# HashUnit3.net
KiCad netlist of a schematic drawn in Altium Designer
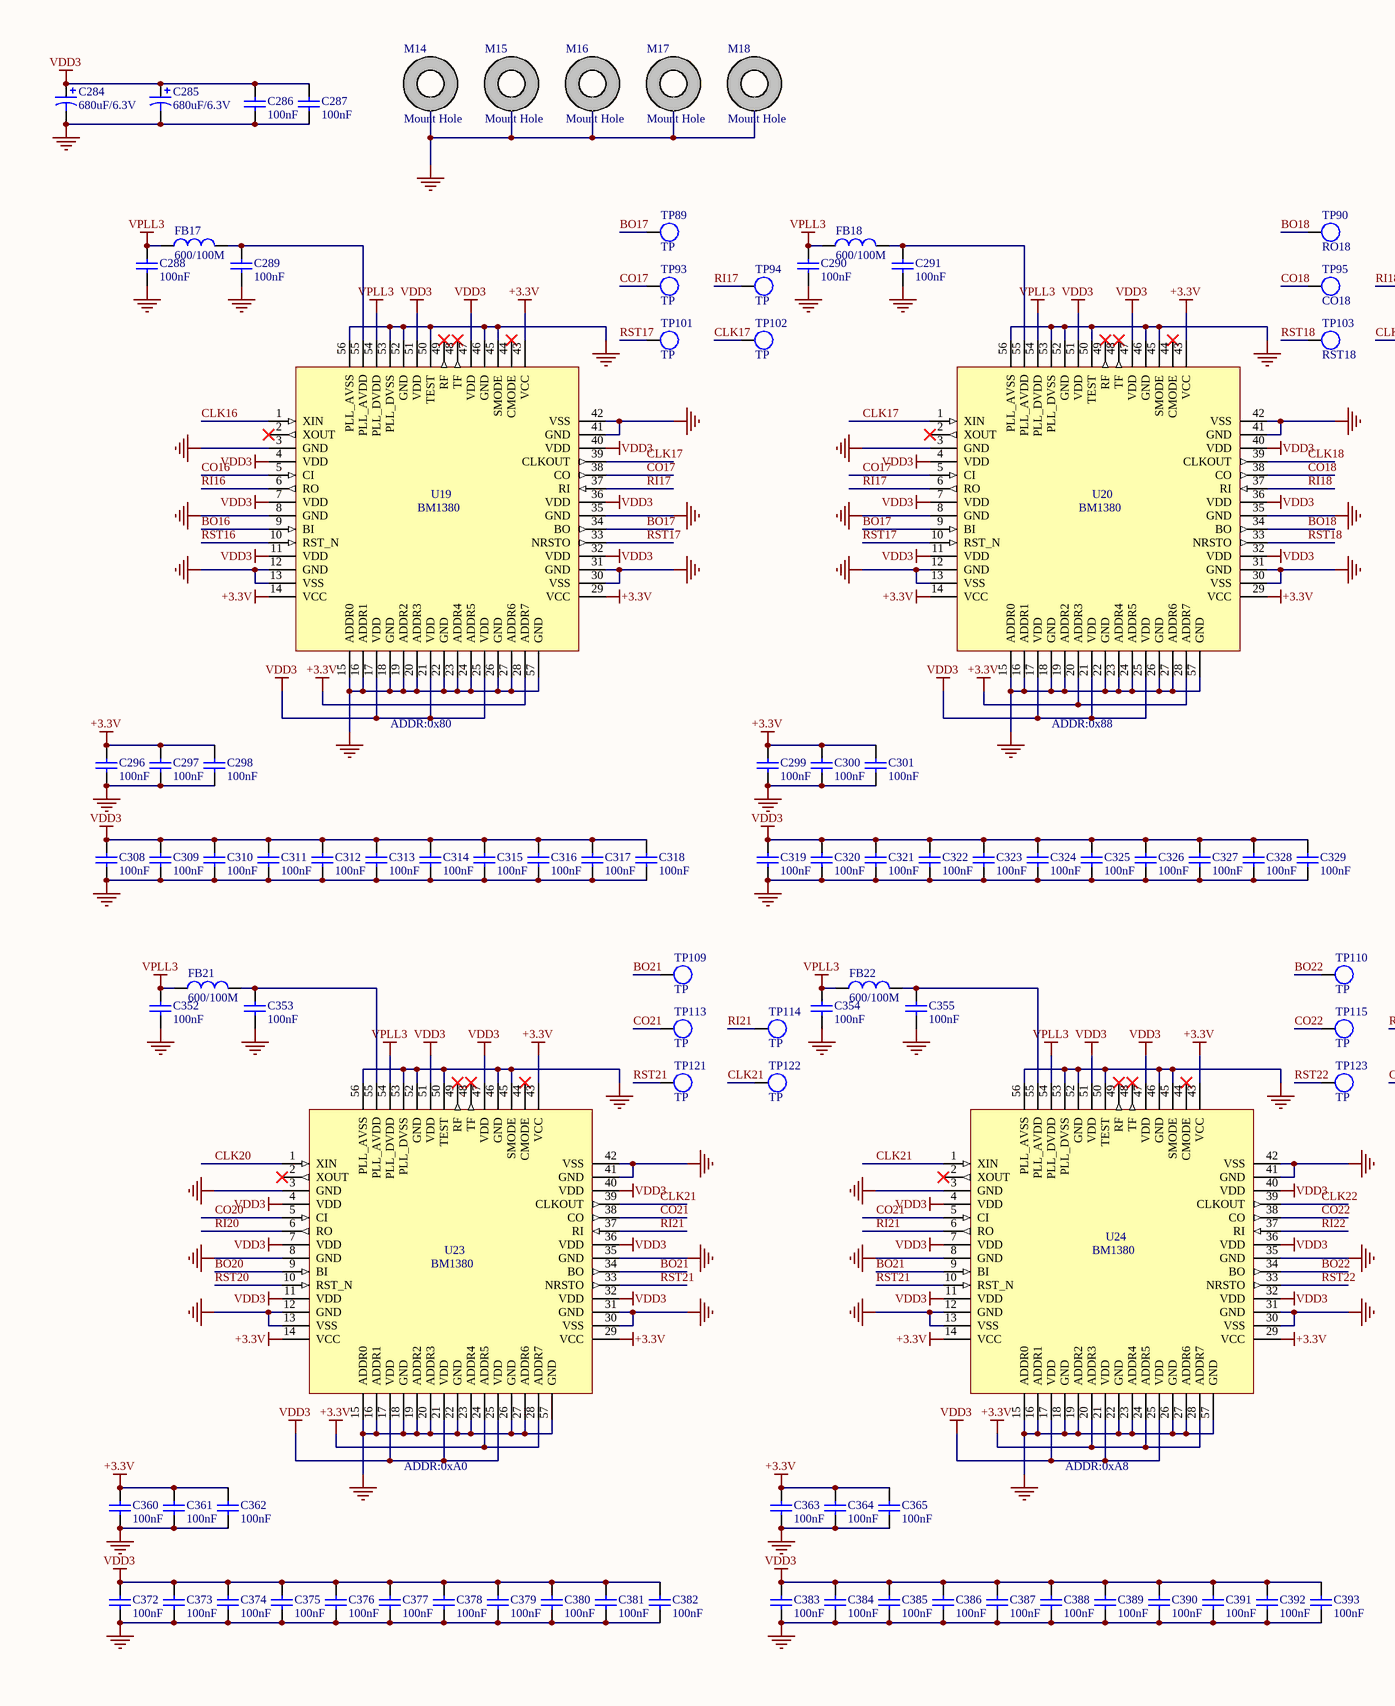
[diagram p0: HashUnit3.SchDoc, left]
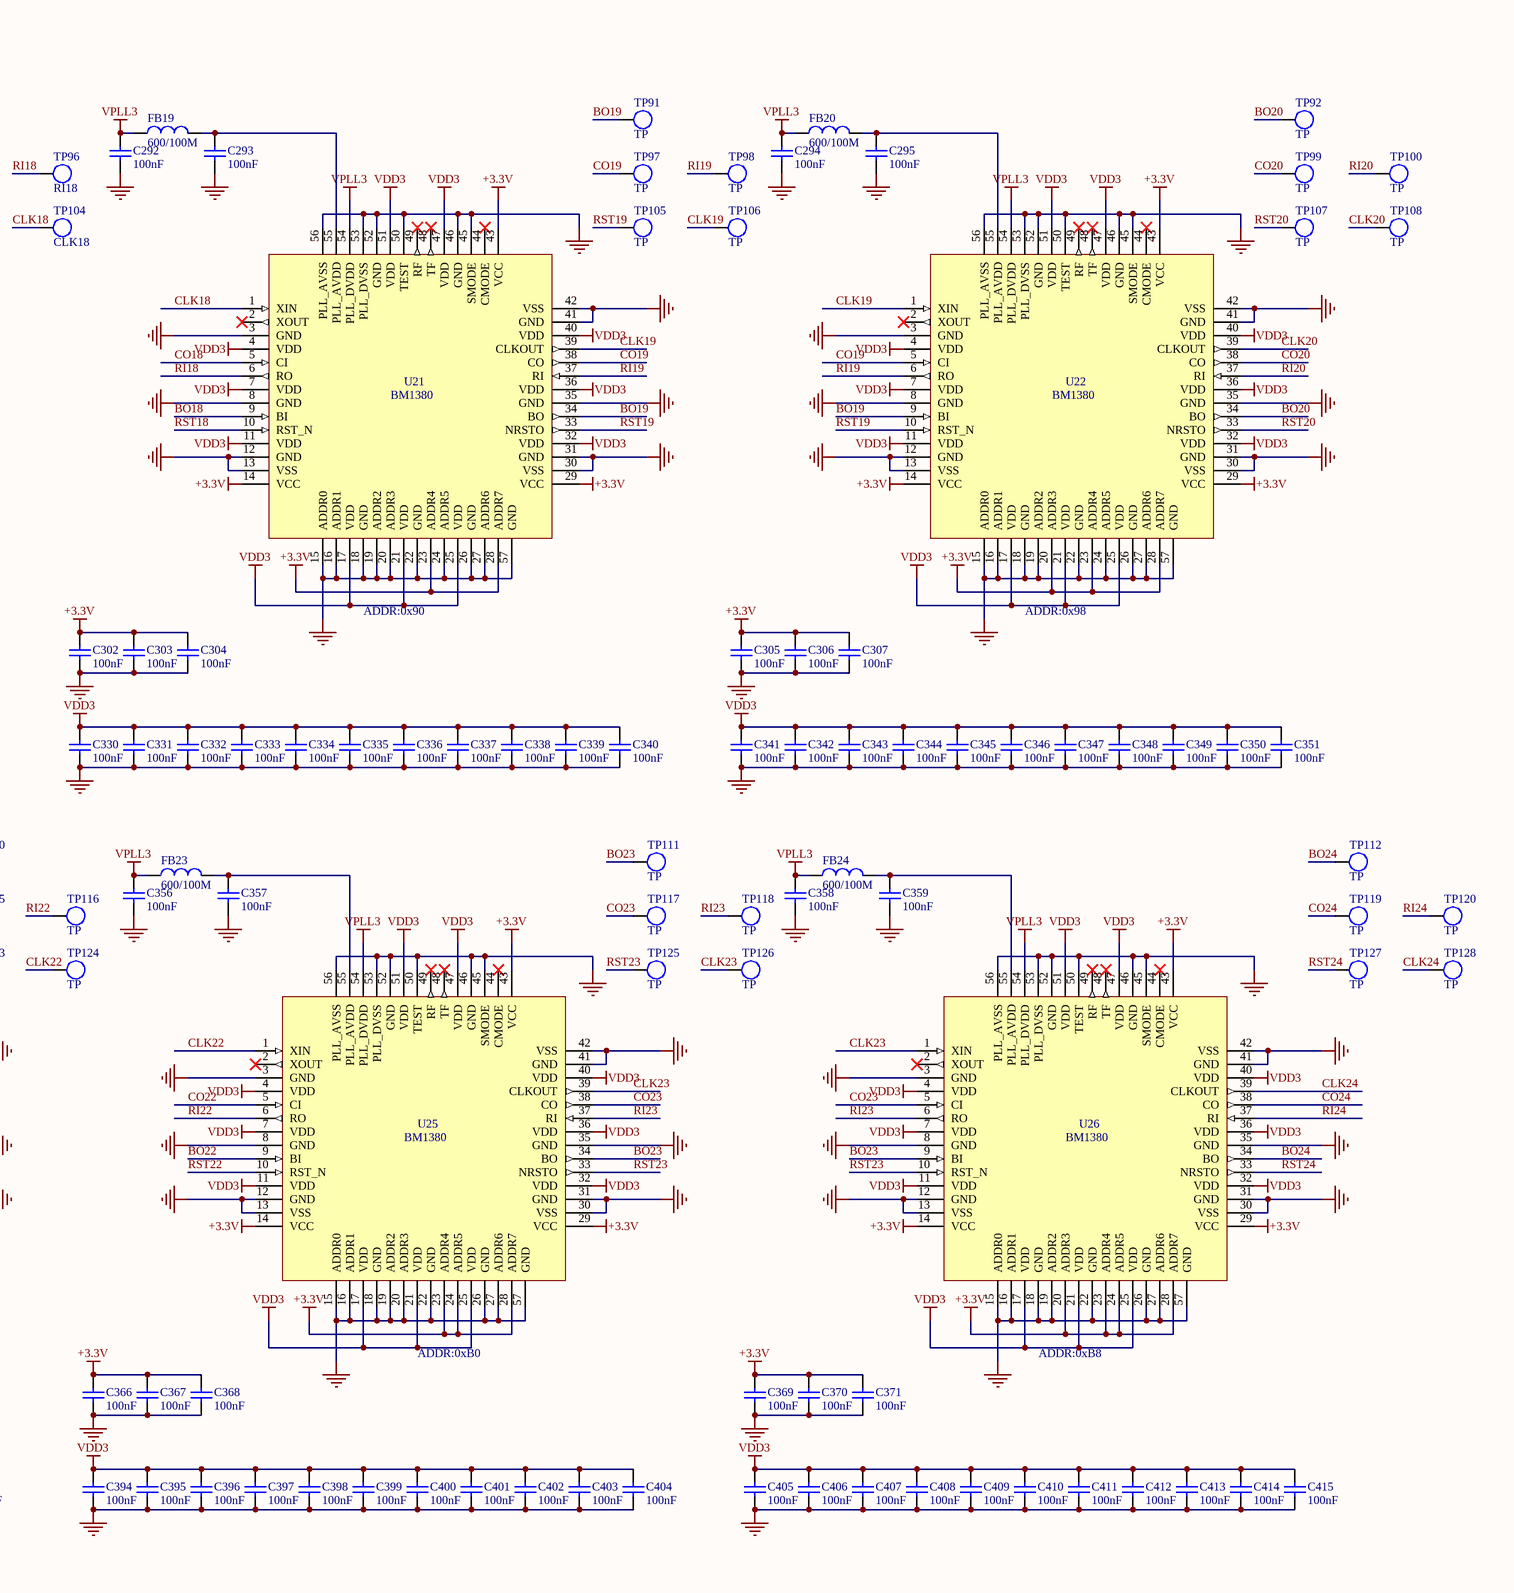
[diagram p1: HashUnit3.SchDoc, right]

(export (version "E")
  (design (tool "Eeschema 10.0.6"))
  (components
    (comp (ref "C284")
      (value "680uF/6.3V")
      (footprint "D")
      (description "Solid Tantalum Chip Capacitor, T492 Series - CWR11 Style Per Mil-PRF-55365/8")
      (fields (field (name "PUBLISHER") "Altium Limited"))
      (libsource (lib "KEMET Chip Capacitor") (part "T492C"))
    )
    (comp (ref "C285")
      (value "680uF/6.3V")
      (footprint "D")
      (description "Solid Tantalum Chip Capacitor, T492 Series - CWR11 Style Per Mil-PRF-55365/8")
      (fields (field (name "PUBLISHER") "Altium Limited"))
      (libsource (lib "KEMET Chip Capacitor") (part "T492C"))
    )
    (comp (ref "C286")
      (value "100nF")
      (footprint "CC0603(1608)")
      (description "Capacitor (Semiconductor SIM Model)")
      (fields (field (name "PUBLISHER") "Altium Limited"))
      (libsource (lib "Miscellaneous Devices") (part "Cap Semi"))
    )
    (comp (ref "C287")
      (value "100nF")
      (footprint "CC0603(1608)")
      (description "Capacitor (Semiconductor SIM Model)")
      (fields (field (name "PUBLISHER") "Altium Limited"))
      (libsource (lib "Miscellaneous Devices") (part "Cap Semi"))
    )
    (comp (ref "C288")
      (value "100nF")
      (footprint "CC0603(1608)")
      (description "Capacitor")
      (fields (field (name "PUBLISHER") "Altium Limited"))
      (libsource (lib "BitMain_Miner_1") (part "Cap"))
    )
    (comp (ref "C289")
      (value "100nF")
      (footprint "CC0603(1608)")
      (description "Capacitor")
      (fields (field (name "PUBLISHER") "Altium Limited"))
      (libsource (lib "BitMain_Miner_1") (part "Cap"))
    )
    (comp (ref "C290")
      (value "100nF")
      (footprint "CC0603(1608)")
      (description "Capacitor")
      (fields (field (name "PUBLISHER") "Altium Limited"))
      (libsource (lib "BitMain_Miner_1") (part "Cap"))
    )
    (comp (ref "C291")
      (value "100nF")
      (footprint "CC0603(1608)")
      (description "Capacitor")
      (fields (field (name "PUBLISHER") "Altium Limited"))
      (libsource (lib "BitMain_Miner_1") (part "Cap"))
    )
    (comp (ref "C292")
      (value "100nF")
      (footprint "CC0603(1608)")
      (description "Capacitor")
      (fields (field (name "PUBLISHER") "Altium Limited"))
      (libsource (lib "BitMain_Miner_1") (part "Cap"))
    )
    (comp (ref "C293")
      (value "100nF")
      (footprint "CC0603(1608)")
      (description "Capacitor")
      (fields (field (name "PUBLISHER") "Altium Limited"))
      (libsource (lib "BitMain_Miner_1") (part "Cap"))
    )
    (comp (ref "C294")
      (value "100nF")
      (footprint "CC0603(1608)")
      (description "Capacitor")
      (fields (field (name "PUBLISHER") "Altium Limited"))
      (libsource (lib "BitMain_Miner_1") (part "Cap"))
    )
    (comp (ref "C295")
      (value "100nF")
      (footprint "CC0603(1608)")
      (description "Capacitor")
      (fields (field (name "PUBLISHER") "Altium Limited"))
      (libsource (lib "BitMain_Miner_1") (part "Cap"))
    )
    (comp (ref "C296")
      (value "100nF")
      (footprint "CC0603(1608)")
      (description "Capacitor")
      (fields (field (name "PUBLISHER") "Altium Limited"))
      (libsource (lib "BitMain_Miner_1") (part "Cap"))
    )
    (comp (ref "C297")
      (value "100nF")
      (footprint "CC0603(1608)")
      (description "Capacitor")
      (fields (field (name "PUBLISHER") "Altium Limited"))
      (libsource (lib "BitMain_Miner_1") (part "Cap"))
    )
    (comp (ref "C298")
      (value "100nF")
      (footprint "CC0603(1608)")
      (description "Capacitor")
      (fields (field (name "PUBLISHER") "Altium Limited"))
      (libsource (lib "BitMain_Miner_1") (part "Cap"))
    )
    (comp (ref "C299")
      (value "100nF")
      (footprint "CC0603(1608)")
      (description "Capacitor")
      (fields (field (name "PUBLISHER") "Altium Limited"))
      (libsource (lib "BitMain_Miner_1") (part "Cap"))
    )
    (comp (ref "C300")
      (value "100nF")
      (footprint "CC0603(1608)")
      (description "Capacitor")
      (fields (field (name "PUBLISHER") "Altium Limited"))
      (libsource (lib "BitMain_Miner_1") (part "Cap"))
    )
    (comp (ref "C301")
      (value "100nF")
      (footprint "CC0603(1608)")
      (description "Capacitor")
      (fields (field (name "PUBLISHER") "Altium Limited"))
      (libsource (lib "BitMain_Miner_1") (part "Cap"))
    )
    (comp (ref "C302")
      (value "100nF")
      (footprint "CC0603(1608)")
      (description "Capacitor")
      (fields (field (name "PUBLISHER") "Altium Limited"))
      (libsource (lib "BitMain_Miner_1") (part "Cap"))
    )
    (comp (ref "C303")
      (value "100nF")
      (footprint "CC0603(1608)")
      (description "Capacitor")
      (fields (field (name "PUBLISHER") "Altium Limited"))
      (libsource (lib "BitMain_Miner_1") (part "Cap"))
    )
    (comp (ref "C304")
      (value "100nF")
      (footprint "CC0603(1608)")
      (description "Capacitor")
      (fields (field (name "PUBLISHER") "Altium Limited"))
      (libsource (lib "BitMain_Miner_1") (part "Cap"))
    )
    (comp (ref "C305")
      (value "100nF")
      (footprint "CC0603(1608)")
      (description "Capacitor")
      (fields (field (name "PUBLISHER") "Altium Limited"))
      (libsource (lib "BitMain_Miner_1") (part "Cap"))
    )
    (comp (ref "C306")
      (value "100nF")
      (footprint "CC0603(1608)")
      (description "Capacitor")
      (fields (field (name "PUBLISHER") "Altium Limited"))
      (libsource (lib "BitMain_Miner_1") (part "Cap"))
    )
    (comp (ref "C307")
      (value "100nF")
      (footprint "CC0603(1608)")
      (description "Capacitor")
      (fields (field (name "PUBLISHER") "Altium Limited"))
      (libsource (lib "BitMain_Miner_1") (part "Cap"))
    )
    (comp (ref "C308")
      (value "100nF")
      (footprint "CC0603(1608)")
      (description "Capacitor")
      (fields (field (name "PUBLISHER") "Altium Limited"))
      (libsource (lib "BitMain_Miner_1") (part "Cap"))
    )
    (comp (ref "C309")
      (value "100nF")
      (footprint "CC0603(1608)")
      (description "Capacitor")
      (fields (field (name "PUBLISHER") "Altium Limited"))
      (libsource (lib "BitMain_Miner_1") (part "Cap"))
    )
    (comp (ref "C310")
      (value "100nF")
      (footprint "CC0603(1608)")
      (description "Capacitor")
      (fields (field (name "PUBLISHER") "Altium Limited"))
      (libsource (lib "BitMain_Miner_1") (part "Cap"))
    )
    (comp (ref "C311")
      (value "100nF")
      (footprint "CC0603(1608)")
      (description "Capacitor")
      (fields (field (name "PUBLISHER") "Altium Limited"))
      (libsource (lib "BitMain_Miner_1") (part "Cap"))
    )
    (comp (ref "C312")
      (value "100nF")
      (footprint "CC0603(1608)")
      (description "Capacitor")
      (fields (field (name "PUBLISHER") "Altium Limited"))
      (libsource (lib "BitMain_Miner_1") (part "Cap"))
    )
    (comp (ref "C313")
      (value "100nF")
      (footprint "CC0603(1608)")
      (description "Capacitor")
      (fields (field (name "PUBLISHER") "Altium Limited"))
      (libsource (lib "BitMain_Miner_1") (part "Cap"))
    )
    (comp (ref "C314")
      (value "100nF")
      (footprint "CC0603(1608)")
      (description "Capacitor")
      (fields (field (name "PUBLISHER") "Altium Limited"))
      (libsource (lib "BitMain_Miner_1") (part "Cap"))
    )
    (comp (ref "C315")
      (value "100nF")
      (footprint "CC0603(1608)")
      (description "Capacitor")
      (fields (field (name "PUBLISHER") "Altium Limited"))
      (libsource (lib "BitMain_Miner_1") (part "Cap"))
    )
    (comp (ref "C316")
      (value "100nF")
      (footprint "CC0603(1608)")
      (description "Capacitor")
      (fields (field (name "PUBLISHER") "Altium Limited"))
      (libsource (lib "BitMain_Miner_1") (part "Cap"))
    )
    (comp (ref "C317")
      (value "100nF")
      (footprint "CC0603(1608)")
      (description "Capacitor")
      (fields (field (name "PUBLISHER") "Altium Limited"))
      (libsource (lib "BitMain_Miner_1") (part "Cap"))
    )
    (comp (ref "C318")
      (value "100nF")
      (footprint "CC0603(1608)")
      (description "Capacitor")
      (fields (field (name "PUBLISHER") "Altium Limited"))
      (libsource (lib "BitMain_Miner_1") (part "Cap"))
    )
    (comp (ref "C319")
      (value "100nF")
      (footprint "CC0603(1608)")
      (description "Capacitor")
      (fields (field (name "PUBLISHER") "Altium Limited"))
      (libsource (lib "BitMain_Miner_1") (part "Cap"))
    )
    (comp (ref "C320")
      (value "100nF")
      (footprint "CC0603(1608)")
      (description "Capacitor")
      (fields (field (name "PUBLISHER") "Altium Limited"))
      (libsource (lib "BitMain_Miner_1") (part "Cap"))
    )
    (comp (ref "C321")
      (value "100nF")
      (footprint "CC0603(1608)")
      (description "Capacitor")
      (fields (field (name "PUBLISHER") "Altium Limited"))
      (libsource (lib "BitMain_Miner_1") (part "Cap"))
    )
    (comp (ref "C322")
      (value "100nF")
      (footprint "CC0603(1608)")
      (description "Capacitor")
      (fields (field (name "PUBLISHER") "Altium Limited"))
      (libsource (lib "BitMain_Miner_1") (part "Cap"))
    )
    (comp (ref "C323")
      (value "100nF")
      (footprint "CC0603(1608)")
      (description "Capacitor")
      (fields (field (name "PUBLISHER") "Altium Limited"))
      (libsource (lib "BitMain_Miner_1") (part "Cap"))
    )
    (comp (ref "C324")
      (value "100nF")
      (footprint "CC0603(1608)")
      (description "Capacitor")
      (fields (field (name "PUBLISHER") "Altium Limited"))
      (libsource (lib "BitMain_Miner_1") (part "Cap"))
    )
    (comp (ref "C325")
      (value "100nF")
      (footprint "CC0603(1608)")
      (description "Capacitor")
      (fields (field (name "PUBLISHER") "Altium Limited"))
      (libsource (lib "BitMain_Miner_1") (part "Cap"))
    )
    (comp (ref "C326")
      (value "100nF")
      (footprint "CC0603(1608)")
      (description "Capacitor")
      (fields (field (name "PUBLISHER") "Altium Limited"))
      (libsource (lib "BitMain_Miner_1") (part "Cap"))
    )
    (comp (ref "C327")
      (value "100nF")
      (footprint "CC0603(1608)")
      (description "Capacitor")
      (fields (field (name "PUBLISHER") "Altium Limited"))
      (libsource (lib "BitMain_Miner_1") (part "Cap"))
    )
    (comp (ref "C328")
      (value "100nF")
      (footprint "CC0603(1608)")
      (description "Capacitor")
      (fields (field (name "PUBLISHER") "Altium Limited"))
      (libsource (lib "BitMain_Miner_1") (part "Cap"))
    )
    (comp (ref "C329")
      (value "100nF")
      (footprint "CC0603(1608)")
      (description "Capacitor")
      (fields (field (name "PUBLISHER") "Altium Limited"))
      (libsource (lib "BitMain_Miner_1") (part "Cap"))
    )
    (comp (ref "C330")
      (value "100nF")
      (footprint "CC0603(1608)")
      (description "Capacitor")
      (fields (field (name "PUBLISHER") "Altium Limited"))
      (libsource (lib "BitMain_Miner_1") (part "Cap"))
    )
    (comp (ref "C331")
      (value "100nF")
      (footprint "CC0603(1608)")
      (description "Capacitor")
      (fields (field (name "PUBLISHER") "Altium Limited"))
      (libsource (lib "BitMain_Miner_1") (part "Cap"))
    )
    (comp (ref "C332")
      (value "100nF")
      (footprint "CC0603(1608)")
      (description "Capacitor")
      (fields (field (name "PUBLISHER") "Altium Limited"))
      (libsource (lib "BitMain_Miner_1") (part "Cap"))
    )
    (comp (ref "C333")
      (value "100nF")
      (footprint "CC0603(1608)")
      (description "Capacitor")
      (fields (field (name "PUBLISHER") "Altium Limited"))
      (libsource (lib "BitMain_Miner_1") (part "Cap"))
    )
    (comp (ref "C334")
      (value "100nF")
      (footprint "CC0603(1608)")
      (description "Capacitor")
      (fields (field (name "PUBLISHER") "Altium Limited"))
      (libsource (lib "BitMain_Miner_1") (part "Cap"))
    )
    (comp (ref "C335")
      (value "100nF")
      (footprint "CC0603(1608)")
      (description "Capacitor")
      (fields (field (name "PUBLISHER") "Altium Limited"))
      (libsource (lib "BitMain_Miner_1") (part "Cap"))
    )
    (comp (ref "C336")
      (value "100nF")
      (footprint "CC0603(1608)")
      (description "Capacitor")
      (fields (field (name "PUBLISHER") "Altium Limited"))
      (libsource (lib "BitMain_Miner_1") (part "Cap"))
    )
    (comp (ref "C337")
      (value "100nF")
      (footprint "CC0603(1608)")
      (description "Capacitor")
      (fields (field (name "PUBLISHER") "Altium Limited"))
      (libsource (lib "BitMain_Miner_1") (part "Cap"))
    )
    (comp (ref "C338")
      (value "100nF")
      (footprint "CC0603(1608)")
      (description "Capacitor")
      (fields (field (name "PUBLISHER") "Altium Limited"))
      (libsource (lib "BitMain_Miner_1") (part "Cap"))
    )
    (comp (ref "C339")
      (value "100nF")
      (footprint "CC0603(1608)")
      (description "Capacitor")
      (fields (field (name "PUBLISHER") "Altium Limited"))
      (libsource (lib "BitMain_Miner_1") (part "Cap"))
    )
    (comp (ref "C340")
      (value "100nF")
      (footprint "CC0603(1608)")
      (description "Capacitor")
      (fields (field (name "PUBLISHER") "Altium Limited"))
      (libsource (lib "BitMain_Miner_1") (part "Cap"))
    )
    (comp (ref "C341")
      (value "100nF")
      (footprint "CC0603(1608)")
      (description "Capacitor")
      (fields (field (name "PUBLISHER") "Altium Limited"))
      (libsource (lib "BitMain_Miner_1") (part "Cap"))
    )
    (comp (ref "C342")
      (value "100nF")
      (footprint "CC0603(1608)")
      (description "Capacitor")
      (fields (field (name "PUBLISHER") "Altium Limited"))
      (libsource (lib "BitMain_Miner_1") (part "Cap"))
    )
    (comp (ref "C343")
      (value "100nF")
      (footprint "CC0603(1608)")
      (description "Capacitor")
      (fields (field (name "PUBLISHER") "Altium Limited"))
      (libsource (lib "BitMain_Miner_1") (part "Cap"))
    )
    (comp (ref "C344")
      (value "100nF")
      (footprint "CC0603(1608)")
      (description "Capacitor")
      (fields (field (name "PUBLISHER") "Altium Limited"))
      (libsource (lib "BitMain_Miner_1") (part "Cap"))
    )
    (comp (ref "C345")
      (value "100nF")
      (footprint "CC0603(1608)")
      (description "Capacitor")
      (fields (field (name "PUBLISHER") "Altium Limited"))
      (libsource (lib "BitMain_Miner_1") (part "Cap"))
    )
    (comp (ref "C346")
      (value "100nF")
      (footprint "CC0603(1608)")
      (description "Capacitor")
      (fields (field (name "PUBLISHER") "Altium Limited"))
      (libsource (lib "BitMain_Miner_1") (part "Cap"))
    )
    (comp (ref "C347")
      (value "100nF")
      (footprint "CC0603(1608)")
      (description "Capacitor")
      (fields (field (name "PUBLISHER") "Altium Limited"))
      (libsource (lib "BitMain_Miner_1") (part "Cap"))
    )
    (comp (ref "C348")
      (value "100nF")
      (footprint "CC0603(1608)")
      (description "Capacitor")
      (fields (field (name "PUBLISHER") "Altium Limited"))
      (libsource (lib "BitMain_Miner_1") (part "Cap"))
    )
    (comp (ref "C349")
      (value "100nF")
      (footprint "CC0603(1608)")
      (description "Capacitor")
      (fields (field (name "PUBLISHER") "Altium Limited"))
      (libsource (lib "BitMain_Miner_1") (part "Cap"))
    )
    (comp (ref "C350")
      (value "100nF")
      (footprint "CC0603(1608)")
      (description "Capacitor")
      (fields (field (name "PUBLISHER") "Altium Limited"))
      (libsource (lib "BitMain_Miner_1") (part "Cap"))
    )
    (comp (ref "C351")
      (value "100nF")
      (footprint "CC0603(1608)")
      (description "Capacitor")
      (fields (field (name "PUBLISHER") "Altium Limited"))
      (libsource (lib "BitMain_Miner_1") (part "Cap"))
    )
    (comp (ref "C352")
      (value "100nF")
      (footprint "CC0603(1608)")
      (description "Capacitor")
      (fields (field (name "PUBLISHER") "Altium Limited"))
      (libsource (lib "BitMain_Miner_1") (part "Cap"))
    )
    (comp (ref "C353")
      (value "100nF")
      (footprint "CC0603(1608)")
      (description "Capacitor")
      (fields (field (name "PUBLISHER") "Altium Limited"))
      (libsource (lib "BitMain_Miner_1") (part "Cap"))
    )
    (comp (ref "C354")
      (value "100nF")
      (footprint "CC0603(1608)")
      (description "Capacitor")
      (fields (field (name "PUBLISHER") "Altium Limited"))
      (libsource (lib "BitMain_Miner_1") (part "Cap"))
    )
    (comp (ref "C355")
      (value "100nF")
      (footprint "CC0603(1608)")
      (description "Capacitor")
      (fields (field (name "PUBLISHER") "Altium Limited"))
      (libsource (lib "BitMain_Miner_1") (part "Cap"))
    )
    (comp (ref "C356")
      (value "100nF")
      (footprint "CC0603(1608)")
      (description "Capacitor")
      (fields (field (name "PUBLISHER") "Altium Limited"))
      (libsource (lib "BitMain_Miner_1") (part "Cap"))
    )
    (comp (ref "C357")
      (value "100nF")
      (footprint "CC0603(1608)")
      (description "Capacitor")
      (fields (field (name "PUBLISHER") "Altium Limited"))
      (libsource (lib "BitMain_Miner_1") (part "Cap"))
    )
    (comp (ref "C358")
      (value "100nF")
      (footprint "CC0603(1608)")
      (description "Capacitor")
      (fields (field (name "PUBLISHER") "Altium Limited"))
      (libsource (lib "BitMain_Miner_1") (part "Cap"))
    )
    (comp (ref "C359")
      (value "100nF")
      (footprint "CC0603(1608)")
      (description "Capacitor")
      (fields (field (name "PUBLISHER") "Altium Limited"))
      (libsource (lib "BitMain_Miner_1") (part "Cap"))
    )
    (comp (ref "C360")
      (value "100nF")
      (footprint "CC0603(1608)")
      (description "Capacitor")
      (fields (field (name "PUBLISHER") "Altium Limited"))
      (libsource (lib "BitMain_Miner_1") (part "Cap"))
    )
    (comp (ref "C361")
      (value "100nF")
      (footprint "CC0603(1608)")
      (description "Capacitor")
      (fields (field (name "PUBLISHER") "Altium Limited"))
      (libsource (lib "BitMain_Miner_1") (part "Cap"))
    )
    (comp (ref "C362")
      (value "100nF")
      (footprint "CC0603(1608)")
      (description "Capacitor")
      (fields (field (name "PUBLISHER") "Altium Limited"))
      (libsource (lib "BitMain_Miner_1") (part "Cap"))
    )
    (comp (ref "C363")
      (value "100nF")
      (footprint "CC0603(1608)")
      (description "Capacitor")
      (fields (field (name "PUBLISHER") "Altium Limited"))
      (libsource (lib "BitMain_Miner_1") (part "Cap"))
    )
    (comp (ref "C364")
      (value "100nF")
      (footprint "CC0603(1608)")
      (description "Capacitor")
      (fields (field (name "PUBLISHER") "Altium Limited"))
      (libsource (lib "BitMain_Miner_1") (part "Cap"))
    )
    (comp (ref "C365")
      (value "100nF")
      (footprint "CC0603(1608)")
      (description "Capacitor")
      (fields (field (name "PUBLISHER") "Altium Limited"))
      (libsource (lib "BitMain_Miner_1") (part "Cap"))
    )
    (comp (ref "C366")
      (value "100nF")
      (footprint "CC0603(1608)")
      (description "Capacitor")
      (fields (field (name "PUBLISHER") "Altium Limited"))
      (libsource (lib "BitMain_Miner_1") (part "Cap"))
    )
    (comp (ref "C367")
      (value "100nF")
      (footprint "CC0603(1608)")
      (description "Capacitor")
      (fields (field (name "PUBLISHER") "Altium Limited"))
      (libsource (lib "BitMain_Miner_1") (part "Cap"))
    )
    (comp (ref "C368")
      (value "100nF")
      (footprint "CC0603(1608)")
      (description "Capacitor")
      (fields (field (name "PUBLISHER") "Altium Limited"))
      (libsource (lib "BitMain_Miner_1") (part "Cap"))
    )
    (comp (ref "C369")
      (value "100nF")
      (footprint "CC0603(1608)")
      (description "Capacitor")
      (fields (field (name "PUBLISHER") "Altium Limited"))
      (libsource (lib "BitMain_Miner_1") (part "Cap"))
    )
    (comp (ref "C370")
      (value "100nF")
      (footprint "CC0603(1608)")
      (description "Capacitor")
      (fields (field (name "PUBLISHER") "Altium Limited"))
      (libsource (lib "BitMain_Miner_1") (part "Cap"))
    )
    (comp (ref "C371")
      (value "100nF")
      (footprint "CC0603(1608)")
      (description "Capacitor")
      (fields (field (name "PUBLISHER") "Altium Limited"))
      (libsource (lib "BitMain_Miner_1") (part "Cap"))
    )
    (comp (ref "C372")
      (value "100nF")
      (footprint "CC0603(1608)")
      (description "Capacitor")
      (fields (field (name "PUBLISHER") "Altium Limited"))
      (libsource (lib "BitMain_Miner_1") (part "Cap"))
    )
    (comp (ref "C373")
      (value "100nF")
      (footprint "CC0603(1608)")
      (description "Capacitor")
      (fields (field (name "PUBLISHER") "Altium Limited"))
      (libsource (lib "BitMain_Miner_1") (part "Cap"))
    )
    (comp (ref "C374")
      (value "100nF")
      (footprint "CC0603(1608)")
      (description "Capacitor")
      (fields (field (name "PUBLISHER") "Altium Limited"))
      (libsource (lib "BitMain_Miner_1") (part "Cap"))
    )
    (comp (ref "C375")
      (value "100nF")
      (footprint "CC0603(1608)")
      (description "Capacitor")
      (fields (field (name "PUBLISHER") "Altium Limited"))
      (libsource (lib "BitMain_Miner_1") (part "Cap"))
    )
    (comp (ref "C376")
      (value "100nF")
      (footprint "CC0603(1608)")
      (description "Capacitor")
      (fields (field (name "PUBLISHER") "Altium Limited"))
      (libsource (lib "BitMain_Miner_1") (part "Cap"))
    )
    (comp (ref "C377")
      (value "100nF")
      (footprint "CC0603(1608)")
      (description "Capacitor")
      (fields (field (name "PUBLISHER") "Altium Limited"))
      (libsource (lib "BitMain_Miner_1") (part "Cap"))
    )
    (comp (ref "C378")
      (value "100nF")
      (footprint "CC0603(1608)")
      (description "Capacitor")
      (fields (field (name "PUBLISHER") "Altium Limited"))
      (libsource (lib "BitMain_Miner_1") (part "Cap"))
    )
    (comp (ref "C379")
      (value "100nF")
      (footprint "CC0603(1608)")
      (description "Capacitor")
      (fields (field (name "PUBLISHER") "Altium Limited"))
      (libsource (lib "BitMain_Miner_1") (part "Cap"))
    )
    (comp (ref "C380")
      (value "100nF")
      (footprint "CC0603(1608)")
      (description "Capacitor")
      (fields (field (name "PUBLISHER") "Altium Limited"))
      (libsource (lib "BitMain_Miner_1") (part "Cap"))
    )
    (comp (ref "C381")
      (value "100nF")
      (footprint "CC0603(1608)")
      (description "Capacitor")
      (fields (field (name "PUBLISHER") "Altium Limited"))
      (libsource (lib "BitMain_Miner_1") (part "Cap"))
    )
    (comp (ref "C382")
      (value "100nF")
      (footprint "CC0603(1608)")
      (description "Capacitor")
      (fields (field (name "PUBLISHER") "Altium Limited"))
      (libsource (lib "BitMain_Miner_1") (part "Cap"))
    )
    (comp (ref "C383")
      (value "100nF")
      (footprint "CC0603(1608)")
      (description "Capacitor")
      (fields (field (name "PUBLISHER") "Altium Limited"))
      (libsource (lib "BitMain_Miner_1") (part "Cap"))
    )
    (comp (ref "C384")
      (value "100nF")
      (footprint "CC0603(1608)")
      (description "Capacitor")
      (fields (field (name "PUBLISHER") "Altium Limited"))
      (libsource (lib "BitMain_Miner_1") (part "Cap"))
    )
    (comp (ref "C385")
      (value "100nF")
      (footprint "CC0603(1608)")
      (description "Capacitor")
      (fields (field (name "PUBLISHER") "Altium Limited"))
      (libsource (lib "BitMain_Miner_1") (part "Cap"))
    )
    (comp (ref "C386")
      (value "100nF")
      (footprint "CC0603(1608)")
      (description "Capacitor")
      (fields (field (name "PUBLISHER") "Altium Limited"))
      (libsource (lib "BitMain_Miner_1") (part "Cap"))
    )
    (comp (ref "C387")
      (value "100nF")
      (footprint "CC0603(1608)")
      (description "Capacitor")
      (fields (field (name "PUBLISHER") "Altium Limited"))
      (libsource (lib "BitMain_Miner_1") (part "Cap"))
    )
    (comp (ref "C388")
      (value "100nF")
      (footprint "CC0603(1608)")
      (description "Capacitor")
      (fields (field (name "PUBLISHER") "Altium Limited"))
      (libsource (lib "BitMain_Miner_1") (part "Cap"))
    )
    (comp (ref "C389")
      (value "100nF")
      (footprint "CC0603(1608)")
      (description "Capacitor")
      (fields (field (name "PUBLISHER") "Altium Limited"))
      (libsource (lib "BitMain_Miner_1") (part "Cap"))
    )
    (comp (ref "C390")
      (value "100nF")
      (footprint "CC0603(1608)")
      (description "Capacitor")
      (fields (field (name "PUBLISHER") "Altium Limited"))
      (libsource (lib "BitMain_Miner_1") (part "Cap"))
    )
    (comp (ref "C391")
      (value "100nF")
      (footprint "CC0603(1608)")
      (description "Capacitor")
      (fields (field (name "PUBLISHER") "Altium Limited"))
      (libsource (lib "BitMain_Miner_1") (part "Cap"))
    )
    (comp (ref "C392")
      (value "100nF")
      (footprint "CC0603(1608)")
      (description "Capacitor")
      (fields (field (name "PUBLISHER") "Altium Limited"))
      (libsource (lib "BitMain_Miner_1") (part "Cap"))
    )
    (comp (ref "C393")
      (value "100nF")
      (footprint "CC0603(1608)")
      (description "Capacitor")
      (fields (field (name "PUBLISHER") "Altium Limited"))
      (libsource (lib "BitMain_Miner_1") (part "Cap"))
    )
    (comp (ref "C394")
      (value "100nF")
      (footprint "CC0603(1608)")
      (description "Capacitor")
      (fields (field (name "PUBLISHER") "Altium Limited"))
      (libsource (lib "BitMain_Miner_1") (part "Cap"))
    )
    (comp (ref "C395")
      (value "100nF")
      (footprint "CC0603(1608)")
      (description "Capacitor")
      (fields (field (name "PUBLISHER") "Altium Limited"))
      (libsource (lib "BitMain_Miner_1") (part "Cap"))
    )
    (comp (ref "C396")
      (value "100nF")
      (footprint "CC0603(1608)")
      (description "Capacitor")
      (fields (field (name "PUBLISHER") "Altium Limited"))
      (libsource (lib "BitMain_Miner_1") (part "Cap"))
    )
    (comp (ref "C397")
      (value "100nF")
      (footprint "CC0603(1608)")
      (description "Capacitor")
      (fields (field (name "PUBLISHER") "Altium Limited"))
      (libsource (lib "BitMain_Miner_1") (part "Cap"))
    )
    (comp (ref "C398")
      (value "100nF")
      (footprint "CC0603(1608)")
      (description "Capacitor")
      (fields (field (name "PUBLISHER") "Altium Limited"))
      (libsource (lib "BitMain_Miner_1") (part "Cap"))
    )
    (comp (ref "C399")
      (value "100nF")
      (footprint "CC0603(1608)")
      (description "Capacitor")
      (fields (field (name "PUBLISHER") "Altium Limited"))
      (libsource (lib "BitMain_Miner_1") (part "Cap"))
    )
    (comp (ref "C400")
      (value "100nF")
      (footprint "CC0603(1608)")
      (description "Capacitor")
      (fields (field (name "PUBLISHER") "Altium Limited"))
      (libsource (lib "BitMain_Miner_1") (part "Cap"))
    )
    (comp (ref "C401")
      (value "100nF")
      (footprint "CC0603(1608)")
      (description "Capacitor")
      (fields (field (name "PUBLISHER") "Altium Limited"))
      (libsource (lib "BitMain_Miner_1") (part "Cap"))
    )
    (comp (ref "C402")
      (value "100nF")
      (footprint "CC0603(1608)")
      (description "Capacitor")
      (fields (field (name "PUBLISHER") "Altium Limited"))
      (libsource (lib "BitMain_Miner_1") (part "Cap"))
    )
    (comp (ref "C403")
      (value "100nF")
      (footprint "CC0603(1608)")
      (description "Capacitor")
      (fields (field (name "PUBLISHER") "Altium Limited"))
      (libsource (lib "BitMain_Miner_1") (part "Cap"))
    )
    (comp (ref "C404")
      (value "100nF")
      (footprint "CC0603(1608)")
      (description "Capacitor")
      (fields (field (name "PUBLISHER") "Altium Limited"))
      (libsource (lib "BitMain_Miner_1") (part "Cap"))
    )
    (comp (ref "C405")
      (value "100nF")
      (footprint "CC0603(1608)")
      (description "Capacitor")
      (fields (field (name "PUBLISHER") "Altium Limited"))
      (libsource (lib "BitMain_Miner_1") (part "Cap"))
    )
    (comp (ref "C406")
      (value "100nF")
      (footprint "CC0603(1608)")
      (description "Capacitor")
      (fields (field (name "PUBLISHER") "Altium Limited"))
      (libsource (lib "BitMain_Miner_1") (part "Cap"))
    )
    (comp (ref "C407")
      (value "100nF")
      (footprint "CC0603(1608)")
      (description "Capacitor")
      (fields (field (name "PUBLISHER") "Altium Limited"))
      (libsource (lib "BitMain_Miner_1") (part "Cap"))
    )
    (comp (ref "C408")
      (value "100nF")
      (footprint "CC0603(1608)")
      (description "Capacitor")
      (fields (field (name "PUBLISHER") "Altium Limited"))
      (libsource (lib "BitMain_Miner_1") (part "Cap"))
    )
    (comp (ref "C409")
      (value "100nF")
      (footprint "CC0603(1608)")
      (description "Capacitor")
      (fields (field (name "PUBLISHER") "Altium Limited"))
      (libsource (lib "BitMain_Miner_1") (part "Cap"))
    )
    (comp (ref "C410")
      (value "100nF")
      (footprint "CC0603(1608)")
      (description "Capacitor")
      (fields (field (name "PUBLISHER") "Altium Limited"))
      (libsource (lib "BitMain_Miner_1") (part "Cap"))
    )
    (comp (ref "C411")
      (value "100nF")
      (footprint "CC0603(1608)")
      (description "Capacitor")
      (fields (field (name "PUBLISHER") "Altium Limited"))
      (libsource (lib "BitMain_Miner_1") (part "Cap"))
    )
    (comp (ref "C412")
      (value "100nF")
      (footprint "CC0603(1608)")
      (description "Capacitor")
      (fields (field (name "PUBLISHER") "Altium Limited"))
      (libsource (lib "BitMain_Miner_1") (part "Cap"))
    )
    (comp (ref "C413")
      (value "100nF")
      (footprint "CC0603(1608)")
      (description "Capacitor")
      (fields (field (name "PUBLISHER") "Altium Limited"))
      (libsource (lib "BitMain_Miner_1") (part "Cap"))
    )
    (comp (ref "C414")
      (value "100nF")
      (footprint "CC0603(1608)")
      (description "Capacitor")
      (fields (field (name "PUBLISHER") "Altium Limited"))
      (libsource (lib "BitMain_Miner_1") (part "Cap"))
    )
    (comp (ref "C415")
      (value "100nF")
      (footprint "CC0603(1608)")
      (description "Capacitor")
      (fields (field (name "PUBLISHER") "Altium Limited"))
      (libsource (lib "BitMain_Miner_1") (part "Cap"))
    )
    (comp (ref "FB17")
      (value "600/100M")
      (footprint "FB0603(1608)")
      (description "Inductor")
      (fields (field (name "PUBLISHER") "Altium Limited"))
      (libsource (lib "BitMain_Miner_1") (part "FB"))
    )
    (comp (ref "FB18")
      (value "600/100M")
      (footprint "FB0603(1608)")
      (description "Inductor")
      (fields (field (name "PUBLISHER") "Altium Limited"))
      (libsource (lib "BitMain_Miner_1") (part "FB"))
    )
    (comp (ref "FB19")
      (value "600/100M")
      (footprint "FB0603(1608)")
      (description "Inductor")
      (fields (field (name "PUBLISHER") "Altium Limited"))
      (libsource (lib "BitMain_Miner_1") (part "FB"))
    )
    (comp (ref "FB20")
      (value "600/100M")
      (footprint "FB0603(1608)")
      (description "Inductor")
      (fields (field (name "PUBLISHER") "Altium Limited"))
      (libsource (lib "BitMain_Miner_1") (part "FB"))
    )
    (comp (ref "FB21")
      (value "600/100M")
      (footprint "FB0603(1608)")
      (description "Inductor")
      (fields (field (name "PUBLISHER") "Altium Limited"))
      (libsource (lib "BitMain_Miner_1") (part "FB"))
    )
    (comp (ref "FB22")
      (value "600/100M")
      (footprint "FB0603(1608)")
      (description "Inductor")
      (fields (field (name "PUBLISHER") "Altium Limited"))
      (libsource (lib "BitMain_Miner_1") (part "FB"))
    )
    (comp (ref "FB23")
      (value "600/100M")
      (footprint "FB0603(1608)")
      (description "Inductor")
      (fields (field (name "PUBLISHER") "Altium Limited"))
      (libsource (lib "BitMain_Miner_1") (part "FB"))
    )
    (comp (ref "FB24")
      (value "600/100M")
      (footprint "FB0603(1608)")
      (description "Inductor")
      (fields (field (name "PUBLISHER") "Altium Limited"))
      (libsource (lib "BitMain_Miner_1") (part "FB"))
    )
    (comp (ref "M14") (value "Mount Hole") (footprint "MHOLE2") (libsource (lib "S6_2") (part "M_Hole")))
    (comp (ref "M15") (value "Mount Hole") (footprint "MHOLE2") (libsource (lib "S6_2") (part "M_Hole")))
    (comp (ref "M16") (value "Mount Hole") (footprint "MHOLE2") (libsource (lib "S6_2") (part "M_Hole")))
    (comp (ref "M17") (value "Mount Hole") (footprint "MHOLE2") (libsource (lib "S6_2") (part "M_Hole")))
    (comp (ref "M18") (value "Mount Hole") (footprint "MHOLE2") (libsource (lib "S6_2") (part "M_Hole")))
    (comp (ref "TP89")
      (value "TP")
      (footprint "TP_SMD")
      (description "Test Point")
      (libsource (lib "BitMain_Miner_1") (part "TP"))
    )
    (comp (ref "TP90")
      (value "RO18")
      (footprint "TP_SMD")
      (description "Test Point")
      (fields (field (name "Comment") "TP"))
      (libsource (lib "BitMain_Miner_1") (part "TP"))
    )
    (comp (ref "TP91")
      (value "TP")
      (footprint "TP_SMD")
      (description "Test Point")
      (libsource (lib "BitMain_Miner_1") (part "TP"))
    )
    (comp (ref "TP92")
      (value "TP")
      (footprint "TP_SMD")
      (description "Test Point")
      (libsource (lib "BitMain_Miner_1") (part "TP"))
    )
    (comp (ref "TP93")
      (value "TP")
      (footprint "TP_SMD")
      (description "Test Point")
      (libsource (lib "BitMain_Miner_1") (part "TP"))
    )
    (comp (ref "TP94")
      (value "TP")
      (footprint "TP_SMD")
      (description "Test Point")
      (libsource (lib "BitMain_Miner_1") (part "TP"))
    )
    (comp (ref "TP95")
      (value "CO18")
      (footprint "TP_SMD")
      (description "Test Point")
      (fields (field (name "Comment") "TP"))
      (libsource (lib "BitMain_Miner_1") (part "TP"))
    )
    (comp (ref "TP96")
      (value "RI18")
      (footprint "TP_SMD")
      (description "Test Point")
      (fields (field (name "Comment") "TP"))
      (libsource (lib "BitMain_Miner_1") (part "TP"))
    )
    (comp (ref "TP97")
      (value "TP")
      (footprint "TP_SMD")
      (description "Test Point")
      (libsource (lib "BitMain_Miner_1") (part "TP"))
    )
    (comp (ref "TP98")
      (value "TP")
      (footprint "TP_SMD")
      (description "Test Point")
      (libsource (lib "BitMain_Miner_1") (part "TP"))
    )
    (comp (ref "TP99")
      (value "TP")
      (footprint "TP_SMD")
      (description "Test Point")
      (libsource (lib "BitMain_Miner_1") (part "TP"))
    )
    (comp (ref "TP100")
      (value "TP")
      (footprint "TP_SMD")
      (description "Test Point")
      (libsource (lib "BitMain_Miner_1") (part "TP"))
    )
    (comp (ref "TP101")
      (value "TP")
      (footprint "TP_SMD")
      (description "Test Point")
      (libsource (lib "BitMain_Miner_1") (part "TP"))
    )
    (comp (ref "TP102")
      (value "TP")
      (footprint "TP_SMD")
      (description "Test Point")
      (libsource (lib "BitMain_Miner_1") (part "TP"))
    )
    (comp (ref "TP103")
      (value "RST18")
      (footprint "TP_SMD")
      (description "Test Point")
      (fields (field (name "Comment") "TP"))
      (libsource (lib "BitMain_Miner_1") (part "TP"))
    )
    (comp (ref "TP104")
      (value "CLK18")
      (footprint "TP_SMD")
      (description "Test Point")
      (fields (field (name "Comment") "TP"))
      (libsource (lib "BitMain_Miner_1") (part "TP"))
    )
    (comp (ref "TP105")
      (value "TP")
      (footprint "TP_SMD")
      (description "Test Point")
      (libsource (lib "BitMain_Miner_1") (part "TP"))
    )
    (comp (ref "TP106")
      (value "TP")
      (footprint "TP_SMD")
      (description "Test Point")
      (libsource (lib "BitMain_Miner_1") (part "TP"))
    )
    (comp (ref "TP107")
      (value "TP")
      (footprint "TP_SMD")
      (description "Test Point")
      (libsource (lib "BitMain_Miner_1") (part "TP"))
    )
    (comp (ref "TP108")
      (value "TP")
      (footprint "TP_SMD")
      (description "Test Point")
      (libsource (lib "BitMain_Miner_1") (part "TP"))
    )
    (comp (ref "TP109")
      (value "TP")
      (footprint "TP_SMD")
      (description "Test Point")
      (libsource (lib "BitMain_Miner_1") (part "TP"))
    )
    (comp (ref "TP110")
      (value "TP")
      (footprint "TP_SMD")
      (description "Test Point")
      (libsource (lib "BitMain_Miner_1") (part "TP"))
    )
    (comp (ref "TP111")
      (value "TP")
      (footprint "TP_SMD")
      (description "Test Point")
      (libsource (lib "BitMain_Miner_1") (part "TP"))
    )
    (comp (ref "TP112")
      (value "TP")
      (footprint "TP_SMD")
      (description "Test Point")
      (libsource (lib "BitMain_Miner_1") (part "TP"))
    )
    (comp (ref "TP113")
      (value "TP")
      (footprint "TP_SMD")
      (description "Test Point")
      (libsource (lib "BitMain_Miner_1") (part "TP"))
    )
    (comp (ref "TP114")
      (value "TP")
      (footprint "TP_SMD")
      (description "Test Point")
      (libsource (lib "BitMain_Miner_1") (part "TP"))
    )
    (comp (ref "TP115")
      (value "TP")
      (footprint "TP_SMD")
      (description "Test Point")
      (libsource (lib "BitMain_Miner_1") (part "TP"))
    )
    (comp (ref "TP116")
      (value "TP")
      (footprint "TP_SMD")
      (description "Test Point")
      (libsource (lib "BitMain_Miner_1") (part "TP"))
    )
    (comp (ref "TP117")
      (value "TP")
      (footprint "TP_SMD")
      (description "Test Point")
      (libsource (lib "BitMain_Miner_1") (part "TP"))
    )
    (comp (ref "TP118")
      (value "TP")
      (footprint "TP_SMD")
      (description "Test Point")
      (libsource (lib "BitMain_Miner_1") (part "TP"))
    )
    (comp (ref "TP119")
      (value "TP")
      (footprint "TP_SMD")
      (description "Test Point")
      (libsource (lib "BitMain_Miner_1") (part "TP"))
    )
    (comp (ref "TP120")
      (value "TP")
      (footprint "TP_SMD")
      (description "Test Point")
      (libsource (lib "BitMain_Miner_1") (part "TP"))
    )
    (comp (ref "TP121")
      (value "TP")
      (footprint "TP_SMD")
      (description "Test Point")
      (libsource (lib "BitMain_Miner_1") (part "TP"))
    )
    (comp (ref "TP122")
      (value "TP")
      (footprint "TP_SMD")
      (description "Test Point")
      (libsource (lib "BitMain_Miner_1") (part "TP"))
    )
    (comp (ref "TP123")
      (value "TP")
      (footprint "TP_SMD")
      (description "Test Point")
      (libsource (lib "BitMain_Miner_1") (part "TP"))
    )
    (comp (ref "TP124")
      (value "TP")
      (footprint "TP_SMD")
      (description "Test Point")
      (libsource (lib "BitMain_Miner_1") (part "TP"))
    )
    (comp (ref "TP125")
      (value "TP")
      (footprint "TP_SMD")
      (description "Test Point")
      (libsource (lib "BitMain_Miner_1") (part "TP"))
    )
    (comp (ref "TP126")
      (value "TP")
      (footprint "TP_SMD")
      (description "Test Point")
      (libsource (lib "BitMain_Miner_1") (part "TP"))
    )
    (comp (ref "TP127")
      (value "TP")
      (footprint "TP_SMD")
      (description "Test Point")
      (libsource (lib "BitMain_Miner_1") (part "TP"))
    )
    (comp (ref "TP128")
      (value "TP")
      (footprint "TP_SMD")
      (description "Test Point")
      (libsource (lib "BitMain_Miner_1") (part "TP"))
    )
    (comp (ref "U19") (value "BM1380") (footprint "QFN56") (libsource (lib "ANT_Miner_V1.3") (part "BM1380")))
    (comp (ref "U20") (value "BM1380") (footprint "QFN56") (libsource (lib "ANT_Miner_V1.3") (part "BM1380")))
    (comp (ref "U21") (value "BM1380") (footprint "QFN56") (libsource (lib "ANT_Miner_V1.3") (part "BM1380")))
    (comp (ref "U22") (value "BM1380") (footprint "QFN56") (libsource (lib "ANT_Miner_V1.3") (part "BM1380")))
    (comp (ref "U23") (value "BM1380") (footprint "QFN56") (libsource (lib "ANT_Miner_V1.3") (part "BM1380")))
    (comp (ref "U24") (value "BM1380") (footprint "QFN56") (libsource (lib "ANT_Miner_V1.3") (part "BM1380")))
    (comp (ref "U25") (value "BM1380") (footprint "QFN56") (libsource (lib "ANT_Miner_V1.3") (part "BM1380")))
    (comp (ref "U26") (value "BM1380") (footprint "QFN56") (libsource (lib "ANT_Miner_V1.3") (part "BM1380")))
  )
  (nets
    (net (code "1") (name "+3.3V") (class "Default")
      (node (ref "C296") (pin "2") (pinfunction "2_2") (pintype "passive"))
      (node (ref "C297") (pin "2") (pinfunction "2_2") (pintype "passive"))
      (node (ref "C298") (pin "2") (pinfunction "2_2") (pintype "passive"))
      (node (ref "C299") (pin "2") (pinfunction "2_2") (pintype "passive"))
      (node (ref "C300") (pin "2") (pinfunction "2_2") (pintype "passive"))
      (node (ref "C301") (pin "2") (pinfunction "2_2") (pintype "passive"))
      (node (ref "C302") (pin "2") (pinfunction "2_2") (pintype "passive"))
      (node (ref "C303") (pin "2") (pinfunction "2_2") (pintype "passive"))
      (node (ref "C304") (pin "2") (pinfunction "2_2") (pintype "passive"))
      (node (ref "C305") (pin "2") (pinfunction "2_2") (pintype "passive"))
      (node (ref "C306") (pin "2") (pinfunction "2_2") (pintype "passive"))
      (node (ref "C307") (pin "2") (pinfunction "2_2") (pintype "passive"))
      (node (ref "C360") (pin "2") (pinfunction "2_2") (pintype "passive"))
      (node (ref "C361") (pin "2") (pinfunction "2_2") (pintype "passive"))
      (node (ref "C362") (pin "2") (pinfunction "2_2") (pintype "passive"))
      (node (ref "C363") (pin "2") (pinfunction "2_2") (pintype "passive"))
      (node (ref "C364") (pin "2") (pinfunction "2_2") (pintype "passive"))
      (node (ref "C365") (pin "2") (pinfunction "2_2") (pintype "passive"))
      (node (ref "C366") (pin "2") (pinfunction "2_2") (pintype "passive"))
      (node (ref "C367") (pin "2") (pinfunction "2_2") (pintype "passive"))
      (node (ref "C368") (pin "2") (pinfunction "2_2") (pintype "passive"))
      (node (ref "C369") (pin "2") (pinfunction "2_2") (pintype "passive"))
      (node (ref "C370") (pin "2") (pinfunction "2_2") (pintype "passive"))
      (node (ref "C371") (pin "2") (pinfunction "2_2") (pintype "passive"))
      (node (ref "U19") (pin "14") (pinfunction "VCC_14") (pintype "power_in"))
      (node (ref "U19") (pin "28") (pinfunction "ADDR7_28") (pintype "passive"))
      (node (ref "U19") (pin "29") (pinfunction "VCC_29") (pintype "power_in"))
      (node (ref "U19") (pin "43") (pinfunction "VCC_43") (pintype "power_in"))
      (node (ref "U20") (pin "14") (pinfunction "VCC_14") (pintype "power_in"))
      (node (ref "U20") (pin "20") (pinfunction "ADDR3_20") (pintype "passive"))
      (node (ref "U20") (pin "28") (pinfunction "ADDR7_28") (pintype "passive"))
      (node (ref "U20") (pin "29") (pinfunction "VCC_29") (pintype "power_in"))
      (node (ref "U20") (pin "43") (pinfunction "VCC_43") (pintype "power_in"))
      (node (ref "U21") (pin "14") (pinfunction "VCC_14") (pintype "power_in"))
      (node (ref "U21") (pin "23") (pinfunction "ADDR4_23") (pintype "passive"))
      (node (ref "U21") (pin "28") (pinfunction "ADDR7_28") (pintype "passive"))
      (node (ref "U21") (pin "29") (pinfunction "VCC_29") (pintype "power_in"))
      (node (ref "U21") (pin "43") (pinfunction "VCC_43") (pintype "power_in"))
      (node (ref "U22") (pin "14") (pinfunction "VCC_14") (pintype "power_in"))
      (node (ref "U22") (pin "20") (pinfunction "ADDR3_20") (pintype "passive"))
      (node (ref "U22") (pin "23") (pinfunction "ADDR4_23") (pintype "passive"))
      (node (ref "U22") (pin "28") (pinfunction "ADDR7_28") (pintype "passive"))
      (node (ref "U22") (pin "29") (pinfunction "VCC_29") (pintype "power_in"))
      (node (ref "U22") (pin "43") (pinfunction "VCC_43") (pintype "power_in"))
      (node (ref "U23") (pin "14") (pinfunction "VCC_14") (pintype "power_in"))
      (node (ref "U23") (pin "24") (pinfunction "ADDR5_24") (pintype "passive"))
      (node (ref "U23") (pin "28") (pinfunction "ADDR7_28") (pintype "passive"))
      (node (ref "U23") (pin "29") (pinfunction "VCC_29") (pintype "power_in"))
      (node (ref "U23") (pin "43") (pinfunction "VCC_43") (pintype "power_in"))
      (node (ref "U24") (pin "14") (pinfunction "VCC_14") (pintype "power_in"))
      (node (ref "U24") (pin "20") (pinfunction "ADDR3_20") (pintype "passive"))
      (node (ref "U24") (pin "24") (pinfunction "ADDR5_24") (pintype "passive"))
      (node (ref "U24") (pin "28") (pinfunction "ADDR7_28") (pintype "passive"))
      (node (ref "U24") (pin "29") (pinfunction "VCC_29") (pintype "power_in"))
      (node (ref "U24") (pin "43") (pinfunction "VCC_43") (pintype "power_in"))
      (node (ref "U25") (pin "14") (pinfunction "VCC_14") (pintype "power_in"))
      (node (ref "U25") (pin "23") (pinfunction "ADDR4_23") (pintype "passive"))
      (node (ref "U25") (pin "24") (pinfunction "ADDR5_24") (pintype "passive"))
      (node (ref "U25") (pin "28") (pinfunction "ADDR7_28") (pintype "passive"))
      (node (ref "U25") (pin "29") (pinfunction "VCC_29") (pintype "power_in"))
      (node (ref "U25") (pin "43") (pinfunction "VCC_43") (pintype "power_in"))
      (node (ref "U26") (pin "14") (pinfunction "VCC_14") (pintype "power_in"))
      (node (ref "U26") (pin "20") (pinfunction "ADDR3_20") (pintype "passive"))
      (node (ref "U26") (pin "23") (pinfunction "ADDR4_23") (pintype "passive"))
      (node (ref "U26") (pin "24") (pinfunction "ADDR5_24") (pintype "passive"))
      (node (ref "U26") (pin "28") (pinfunction "ADDR7_28") (pintype "passive"))
      (node (ref "U26") (pin "29") (pinfunction "VCC_29") (pintype "power_in"))
      (node (ref "U26") (pin "43") (pinfunction "VCC_43") (pintype "power_in"))
    )
    (net (code "2") (name "/BO16") (class "Default")
      (node (ref "U19") (pin "9") (pinfunction "BI_9") (pintype "input"))
    )
    (net (code "3") (name "/BO17") (class "Default")
      (node (ref "TP89") (pin "1") (pinfunction "1_1") (pintype "passive"))
      (node (ref "U19") (pin "34") (pinfunction "BO_34") (pintype "output"))
      (node (ref "U20") (pin "9") (pinfunction "BI_9") (pintype "input"))
    )
    (net (code "4") (name "/BO18") (class "Default")
      (node (ref "TP90") (pin "1") (pinfunction "1_1") (pintype "passive"))
      (node (ref "U20") (pin "34") (pinfunction "BO_34") (pintype "output"))
      (node (ref "U21") (pin "9") (pinfunction "BI_9") (pintype "input"))
    )
    (net (code "5") (name "/BO19") (class "Default")
      (node (ref "TP91") (pin "1") (pinfunction "1_1") (pintype "passive"))
      (node (ref "U21") (pin "34") (pinfunction "BO_34") (pintype "output"))
      (node (ref "U22") (pin "9") (pinfunction "BI_9") (pintype "input"))
    )
    (net (code "6") (name "/BO20") (class "Default")
      (node (ref "TP92") (pin "1") (pinfunction "1_1") (pintype "passive"))
      (node (ref "U22") (pin "34") (pinfunction "BO_34") (pintype "output"))
      (node (ref "U23") (pin "9") (pinfunction "BI_9") (pintype "input"))
    )
    (net (code "7") (name "/BO21") (class "Default")
      (node (ref "TP109") (pin "1") (pinfunction "1_1") (pintype "passive"))
      (node (ref "U23") (pin "34") (pinfunction "BO_34") (pintype "output"))
      (node (ref "U24") (pin "9") (pinfunction "BI_9") (pintype "input"))
    )
    (net (code "8") (name "/BO22") (class "Default")
      (node (ref "TP110") (pin "1") (pinfunction "1_1") (pintype "passive"))
      (node (ref "U24") (pin "34") (pinfunction "BO_34") (pintype "output"))
      (node (ref "U25") (pin "9") (pinfunction "BI_9") (pintype "input"))
    )
    (net (code "9") (name "/BO23") (class "Default")
      (node (ref "TP111") (pin "1") (pinfunction "1_1") (pintype "passive"))
      (node (ref "U25") (pin "34") (pinfunction "BO_34") (pintype "output"))
      (node (ref "U26") (pin "9") (pinfunction "BI_9") (pintype "input"))
    )
    (net (code "10") (name "/BO24") (class "Default")
      (node (ref "TP112") (pin "1") (pinfunction "1_1") (pintype "passive"))
      (node (ref "U26") (pin "34") (pinfunction "BO_34") (pintype "output"))
    )
    (net (code "11") (name "/CLK16") (class "Default")
      (node (ref "U19") (pin "1") (pinfunction "XIN_1") (pintype "input"))
    )
    (net (code "12") (name "/CLK17") (class "Default")
      (node (ref "TP102") (pin "1") (pinfunction "1_1") (pintype "passive"))
      (node (ref "U19") (pin "39") (pinfunction "CLKOUT_39") (pintype "output"))
      (node (ref "U20") (pin "1") (pinfunction "XIN_1") (pintype "input"))
    )
    (net (code "13") (name "/CLK18") (class "Default")
      (node (ref "TP104") (pin "1") (pinfunction "1_1") (pintype "passive"))
      (node (ref "U20") (pin "39") (pinfunction "CLKOUT_39") (pintype "output"))
      (node (ref "U21") (pin "1") (pinfunction "XIN_1") (pintype "input"))
    )
    (net (code "14") (name "/CLK19") (class "Default")
      (node (ref "TP106") (pin "1") (pinfunction "1_1") (pintype "passive"))
      (node (ref "U21") (pin "39") (pinfunction "CLKOUT_39") (pintype "output"))
      (node (ref "U22") (pin "1") (pinfunction "XIN_1") (pintype "input"))
    )
    (net (code "15") (name "/CLK20") (class "Default")
      (node (ref "TP108") (pin "1") (pinfunction "1_1") (pintype "passive"))
      (node (ref "U22") (pin "39") (pinfunction "CLKOUT_39") (pintype "output"))
      (node (ref "U23") (pin "1") (pinfunction "XIN_1") (pintype "input"))
    )
    (net (code "16") (name "/CLK21") (class "Default")
      (node (ref "TP122") (pin "1") (pinfunction "1_1") (pintype "passive"))
      (node (ref "U23") (pin "39") (pinfunction "CLKOUT_39") (pintype "output"))
      (node (ref "U24") (pin "1") (pinfunction "XIN_1") (pintype "input"))
    )
    (net (code "17") (name "/CLK22") (class "Default")
      (node (ref "TP124") (pin "1") (pinfunction "1_1") (pintype "passive"))
      (node (ref "U24") (pin "39") (pinfunction "CLKOUT_39") (pintype "output"))
      (node (ref "U25") (pin "1") (pinfunction "XIN_1") (pintype "input"))
    )
    (net (code "18") (name "/CLK23") (class "Default")
      (node (ref "TP126") (pin "1") (pinfunction "1_1") (pintype "passive"))
      (node (ref "U25") (pin "39") (pinfunction "CLKOUT_39") (pintype "output"))
      (node (ref "U26") (pin "1") (pinfunction "XIN_1") (pintype "input"))
    )
    (net (code "19") (name "/CLK24") (class "Default")
      (node (ref "TP128") (pin "1") (pinfunction "1_1") (pintype "passive"))
      (node (ref "U26") (pin "39") (pinfunction "CLKOUT_39") (pintype "output"))
    )
    (net (code "20") (name "/CO16") (class "Default")
      (node (ref "U19") (pin "5") (pinfunction "CI_5") (pintype "input"))
    )
    (net (code "21") (name "/CO17") (class "Default")
      (node (ref "TP93") (pin "1") (pinfunction "1_1") (pintype "passive"))
      (node (ref "U19") (pin "38") (pinfunction "CO_38") (pintype "output"))
      (node (ref "U20") (pin "5") (pinfunction "CI_5") (pintype "input"))
    )
    (net (code "22") (name "/CO18") (class "Default")
      (node (ref "TP95") (pin "1") (pinfunction "1_1") (pintype "passive"))
      (node (ref "U20") (pin "38") (pinfunction "CO_38") (pintype "output"))
      (node (ref "U21") (pin "5") (pinfunction "CI_5") (pintype "input"))
    )
    (net (code "23") (name "/CO19") (class "Default")
      (node (ref "TP97") (pin "1") (pinfunction "1_1") (pintype "passive"))
      (node (ref "U21") (pin "38") (pinfunction "CO_38") (pintype "output"))
      (node (ref "U22") (pin "5") (pinfunction "CI_5") (pintype "input"))
    )
    (net (code "24") (name "/CO20") (class "Default")
      (node (ref "TP99") (pin "1") (pinfunction "1_1") (pintype "passive"))
      (node (ref "U22") (pin "38") (pinfunction "CO_38") (pintype "output"))
      (node (ref "U23") (pin "5") (pinfunction "CI_5") (pintype "input"))
    )
    (net (code "25") (name "/CO21") (class "Default")
      (node (ref "TP113") (pin "1") (pinfunction "1_1") (pintype "passive"))
      (node (ref "U23") (pin "38") (pinfunction "CO_38") (pintype "output"))
      (node (ref "U24") (pin "5") (pinfunction "CI_5") (pintype "input"))
    )
    (net (code "26") (name "/CO22") (class "Default")
      (node (ref "TP115") (pin "1") (pinfunction "1_1") (pintype "passive"))
      (node (ref "U24") (pin "38") (pinfunction "CO_38") (pintype "output"))
      (node (ref "U25") (pin "5") (pinfunction "CI_5") (pintype "input"))
    )
    (net (code "27") (name "/CO23") (class "Default")
      (node (ref "TP117") (pin "1") (pinfunction "1_1") (pintype "passive"))
      (node (ref "U25") (pin "38") (pinfunction "CO_38") (pintype "output"))
      (node (ref "U26") (pin "5") (pinfunction "CI_5") (pintype "input"))
    )
    (net (code "28") (name "/CO24") (class "Default")
      (node (ref "TP119") (pin "1") (pinfunction "1_1") (pintype "passive"))
      (node (ref "U26") (pin "38") (pinfunction "CO_38") (pintype "output"))
    )
    (net (code "29") (name "/RI16") (class "Default")
      (node (ref "U19") (pin "6") (pinfunction "RO_6") (pintype "output"))
    )
    (net (code "30") (name "/RI17") (class "Default")
      (node (ref "TP94") (pin "1") (pinfunction "1_1") (pintype "passive"))
      (node (ref "U19") (pin "37") (pinfunction "RI_37") (pintype "input"))
      (node (ref "U20") (pin "6") (pinfunction "RO_6") (pintype "output"))
    )
    (net (code "31") (name "/RI18") (class "Default")
      (node (ref "TP96") (pin "1") (pinfunction "1_1") (pintype "passive"))
      (node (ref "U20") (pin "37") (pinfunction "RI_37") (pintype "input"))
      (node (ref "U21") (pin "6") (pinfunction "RO_6") (pintype "output"))
    )
    (net (code "32") (name "/RI19") (class "Default")
      (node (ref "TP98") (pin "1") (pinfunction "1_1") (pintype "passive"))
      (node (ref "U21") (pin "37") (pinfunction "RI_37") (pintype "input"))
      (node (ref "U22") (pin "6") (pinfunction "RO_6") (pintype "output"))
    )
    (net (code "33") (name "/RI20") (class "Default")
      (node (ref "TP100") (pin "1") (pinfunction "1_1") (pintype "passive"))
      (node (ref "U22") (pin "37") (pinfunction "RI_37") (pintype "input"))
      (node (ref "U23") (pin "6") (pinfunction "RO_6") (pintype "output"))
    )
    (net (code "34") (name "/RI21") (class "Default")
      (node (ref "TP114") (pin "1") (pinfunction "1_1") (pintype "passive"))
      (node (ref "U23") (pin "37") (pinfunction "RI_37") (pintype "input"))
      (node (ref "U24") (pin "6") (pinfunction "RO_6") (pintype "output"))
    )
    (net (code "35") (name "/RI22") (class "Default")
      (node (ref "TP116") (pin "1") (pinfunction "1_1") (pintype "passive"))
      (node (ref "U24") (pin "37") (pinfunction "RI_37") (pintype "input"))
      (node (ref "U25") (pin "6") (pinfunction "RO_6") (pintype "output"))
    )
    (net (code "36") (name "/RI23") (class "Default")
      (node (ref "TP118") (pin "1") (pinfunction "1_1") (pintype "passive"))
      (node (ref "U25") (pin "37") (pinfunction "RI_37") (pintype "input"))
      (node (ref "U26") (pin "6") (pinfunction "RO_6") (pintype "output"))
    )
    (net (code "37") (name "/RI24") (class "Default")
      (node (ref "TP120") (pin "1") (pinfunction "1_1") (pintype "passive"))
      (node (ref "U26") (pin "37") (pinfunction "RI_37") (pintype "input"))
    )
    (net (code "38") (name "/RST16") (class "Default")
      (node (ref "U19") (pin "10") (pinfunction "RST_N_10") (pintype "input"))
    )
    (net (code "39") (name "/RST17") (class "Default")
      (node (ref "TP101") (pin "1") (pinfunction "1_1") (pintype "passive"))
      (node (ref "U19") (pin "33") (pinfunction "NRSTO_33") (pintype "output"))
      (node (ref "U20") (pin "10") (pinfunction "RST_N_10") (pintype "input"))
    )
    (net (code "40") (name "/RST18") (class "Default")
      (node (ref "TP103") (pin "1") (pinfunction "1_1") (pintype "passive"))
      (node (ref "U20") (pin "33") (pinfunction "NRSTO_33") (pintype "output"))
      (node (ref "U21") (pin "10") (pinfunction "RST_N_10") (pintype "input"))
    )
    (net (code "41") (name "/RST19") (class "Default")
      (node (ref "TP105") (pin "1") (pinfunction "1_1") (pintype "passive"))
      (node (ref "U21") (pin "33") (pinfunction "NRSTO_33") (pintype "output"))
      (node (ref "U22") (pin "10") (pinfunction "RST_N_10") (pintype "input"))
    )
    (net (code "42") (name "/RST20") (class "Default")
      (node (ref "TP107") (pin "1") (pinfunction "1_1") (pintype "passive"))
      (node (ref "U22") (pin "33") (pinfunction "NRSTO_33") (pintype "output"))
      (node (ref "U23") (pin "10") (pinfunction "RST_N_10") (pintype "input"))
    )
    (net (code "43") (name "/RST21") (class "Default")
      (node (ref "TP121") (pin "1") (pinfunction "1_1") (pintype "passive"))
      (node (ref "U23") (pin "33") (pinfunction "NRSTO_33") (pintype "output"))
      (node (ref "U24") (pin "10") (pinfunction "RST_N_10") (pintype "input"))
    )
    (net (code "44") (name "/RST22") (class "Default")
      (node (ref "TP123") (pin "1") (pinfunction "1_1") (pintype "passive"))
      (node (ref "U24") (pin "33") (pinfunction "NRSTO_33") (pintype "output"))
      (node (ref "U25") (pin "10") (pinfunction "RST_N_10") (pintype "input"))
    )
    (net (code "45") (name "/RST23") (class "Default")
      (node (ref "TP125") (pin "1") (pinfunction "1_1") (pintype "passive"))
      (node (ref "U25") (pin "33") (pinfunction "NRSTO_33") (pintype "output"))
      (node (ref "U26") (pin "10") (pinfunction "RST_N_10") (pintype "input"))
    )
    (net (code "46") (name "/RST24") (class "Default")
      (node (ref "TP127") (pin "1") (pinfunction "1_1") (pintype "passive"))
      (node (ref "U26") (pin "33") (pinfunction "NRSTO_33") (pintype "output"))
    )
    (net (code "47") (name "GND") (class "Default")
      (node (ref "C284") (pin "2") (pinfunction "2_2") (pintype "passive"))
      (node (ref "C285") (pin "2") (pinfunction "2_2") (pintype "passive"))
      (node (ref "C286") (pin "1") (pinfunction "1_1") (pintype "passive"))
      (node (ref "C287") (pin "1") (pinfunction "1_1") (pintype "passive"))
      (node (ref "C288") (pin "2") (pinfunction "2_2") (pintype "passive"))
      (node (ref "C289") (pin "1") (pinfunction "1_1") (pintype "passive"))
      (node (ref "C290") (pin "2") (pinfunction "2_2") (pintype "passive"))
      (node (ref "C291") (pin "1") (pinfunction "1_1") (pintype "passive"))
      (node (ref "C292") (pin "2") (pinfunction "2_2") (pintype "passive"))
      (node (ref "C293") (pin "1") (pinfunction "1_1") (pintype "passive"))
      (node (ref "C294") (pin "2") (pinfunction "2_2") (pintype "passive"))
      (node (ref "C295") (pin "1") (pinfunction "1_1") (pintype "passive"))
      (node (ref "C296") (pin "1") (pinfunction "1_1") (pintype "passive"))
      (node (ref "C297") (pin "1") (pinfunction "1_1") (pintype "passive"))
      (node (ref "C298") (pin "1") (pinfunction "1_1") (pintype "passive"))
      (node (ref "C299") (pin "1") (pinfunction "1_1") (pintype "passive"))
      (node (ref "C300") (pin "1") (pinfunction "1_1") (pintype "passive"))
      (node (ref "C301") (pin "1") (pinfunction "1_1") (pintype "passive"))
      (node (ref "C302") (pin "1") (pinfunction "1_1") (pintype "passive"))
      (node (ref "C303") (pin "1") (pinfunction "1_1") (pintype "passive"))
      (node (ref "C304") (pin "1") (pinfunction "1_1") (pintype "passive"))
      (node (ref "C305") (pin "1") (pinfunction "1_1") (pintype "passive"))
      (node (ref "C306") (pin "1") (pinfunction "1_1") (pintype "passive"))
      (node (ref "C307") (pin "1") (pinfunction "1_1") (pintype "passive"))
      (node (ref "C308") (pin "1") (pinfunction "1_1") (pintype "passive"))
      (node (ref "C309") (pin "1") (pinfunction "1_1") (pintype "passive"))
      (node (ref "C310") (pin "1") (pinfunction "1_1") (pintype "passive"))
      (node (ref "C311") (pin "1") (pinfunction "1_1") (pintype "passive"))
      (node (ref "C312") (pin "1") (pinfunction "1_1") (pintype "passive"))
      (node (ref "C313") (pin "1") (pinfunction "1_1") (pintype "passive"))
      (node (ref "C314") (pin "1") (pinfunction "1_1") (pintype "passive"))
      (node (ref "C315") (pin "1") (pinfunction "1_1") (pintype "passive"))
      (node (ref "C316") (pin "1") (pinfunction "1_1") (pintype "passive"))
      (node (ref "C317") (pin "1") (pinfunction "1_1") (pintype "passive"))
      (node (ref "C318") (pin "1") (pinfunction "1_1") (pintype "passive"))
      (node (ref "C319") (pin "1") (pinfunction "1_1") (pintype "passive"))
      (node (ref "C320") (pin "1") (pinfunction "1_1") (pintype "passive"))
      (node (ref "C321") (pin "1") (pinfunction "1_1") (pintype "passive"))
      (node (ref "C322") (pin "1") (pinfunction "1_1") (pintype "passive"))
      (node (ref "C323") (pin "1") (pinfunction "1_1") (pintype "passive"))
      (node (ref "C324") (pin "1") (pinfunction "1_1") (pintype "passive"))
      (node (ref "C325") (pin "1") (pinfunction "1_1") (pintype "passive"))
      (node (ref "C326") (pin "1") (pinfunction "1_1") (pintype "passive"))
      (node (ref "C327") (pin "1") (pinfunction "1_1") (pintype "passive"))
      (node (ref "C328") (pin "1") (pinfunction "1_1") (pintype "passive"))
      (node (ref "C329") (pin "1") (pinfunction "1_1") (pintype "passive"))
      (node (ref "C330") (pin "1") (pinfunction "1_1") (pintype "passive"))
      (node (ref "C331") (pin "1") (pinfunction "1_1") (pintype "passive"))
      (node (ref "C332") (pin "1") (pinfunction "1_1") (pintype "passive"))
      (node (ref "C333") (pin "1") (pinfunction "1_1") (pintype "passive"))
      (node (ref "C334") (pin "1") (pinfunction "1_1") (pintype "passive"))
      (node (ref "C335") (pin "1") (pinfunction "1_1") (pintype "passive"))
      (node (ref "C336") (pin "1") (pinfunction "1_1") (pintype "passive"))
      (node (ref "C337") (pin "1") (pinfunction "1_1") (pintype "passive"))
      (node (ref "C338") (pin "1") (pinfunction "1_1") (pintype "passive"))
      (node (ref "C339") (pin "1") (pinfunction "1_1") (pintype "passive"))
      (node (ref "C340") (pin "1") (pinfunction "1_1") (pintype "passive"))
      (node (ref "C341") (pin "1") (pinfunction "1_1") (pintype "passive"))
      (node (ref "C342") (pin "1") (pinfunction "1_1") (pintype "passive"))
      (node (ref "C343") (pin "1") (pinfunction "1_1") (pintype "passive"))
      (node (ref "C344") (pin "1") (pinfunction "1_1") (pintype "passive"))
      (node (ref "C345") (pin "1") (pinfunction "1_1") (pintype "passive"))
      (node (ref "C346") (pin "1") (pinfunction "1_1") (pintype "passive"))
      (node (ref "C347") (pin "1") (pinfunction "1_1") (pintype "passive"))
      (node (ref "C348") (pin "1") (pinfunction "1_1") (pintype "passive"))
      (node (ref "C349") (pin "1") (pinfunction "1_1") (pintype "passive"))
      (node (ref "C350") (pin "1") (pinfunction "1_1") (pintype "passive"))
      (node (ref "C351") (pin "1") (pinfunction "1_1") (pintype "passive"))
      (node (ref "C352") (pin "2") (pinfunction "2_2") (pintype "passive"))
      (node (ref "C353") (pin "1") (pinfunction "1_1") (pintype "passive"))
      (node (ref "C354") (pin "2") (pinfunction "2_2") (pintype "passive"))
      (node (ref "C355") (pin "1") (pinfunction "1_1") (pintype "passive"))
      (node (ref "C356") (pin "2") (pinfunction "2_2") (pintype "passive"))
      (node (ref "C357") (pin "1") (pinfunction "1_1") (pintype "passive"))
      (node (ref "C358") (pin "2") (pinfunction "2_2") (pintype "passive"))
      (node (ref "C359") (pin "1") (pinfunction "1_1") (pintype "passive"))
      (node (ref "C360") (pin "1") (pinfunction "1_1") (pintype "passive"))
      (node (ref "C361") (pin "1") (pinfunction "1_1") (pintype "passive"))
      (node (ref "C362") (pin "1") (pinfunction "1_1") (pintype "passive"))
      (node (ref "C363") (pin "1") (pinfunction "1_1") (pintype "passive"))
      (node (ref "C364") (pin "1") (pinfunction "1_1") (pintype "passive"))
      (node (ref "C365") (pin "1") (pinfunction "1_1") (pintype "passive"))
      (node (ref "C366") (pin "1") (pinfunction "1_1") (pintype "passive"))
      (node (ref "C367") (pin "1") (pinfunction "1_1") (pintype "passive"))
      (node (ref "C368") (pin "1") (pinfunction "1_1") (pintype "passive"))
      (node (ref "C369") (pin "1") (pinfunction "1_1") (pintype "passive"))
      (node (ref "C370") (pin "1") (pinfunction "1_1") (pintype "passive"))
      (node (ref "C371") (pin "1") (pinfunction "1_1") (pintype "passive"))
      (node (ref "C372") (pin "1") (pinfunction "1_1") (pintype "passive"))
      (node (ref "C373") (pin "1") (pinfunction "1_1") (pintype "passive"))
      (node (ref "C374") (pin "1") (pinfunction "1_1") (pintype "passive"))
      (node (ref "C375") (pin "1") (pinfunction "1_1") (pintype "passive"))
      (node (ref "C376") (pin "1") (pinfunction "1_1") (pintype "passive"))
      (node (ref "C377") (pin "1") (pinfunction "1_1") (pintype "passive"))
      (node (ref "C378") (pin "1") (pinfunction "1_1") (pintype "passive"))
      (node (ref "C379") (pin "1") (pinfunction "1_1") (pintype "passive"))
      (node (ref "C380") (pin "1") (pinfunction "1_1") (pintype "passive"))
      (node (ref "C381") (pin "1") (pinfunction "1_1") (pintype "passive"))
      (node (ref "C382") (pin "1") (pinfunction "1_1") (pintype "passive"))
      (node (ref "C383") (pin "1") (pinfunction "1_1") (pintype "passive"))
      (node (ref "C384") (pin "1") (pinfunction "1_1") (pintype "passive"))
      (node (ref "C385") (pin "1") (pinfunction "1_1") (pintype "passive"))
      (node (ref "C386") (pin "1") (pinfunction "1_1") (pintype "passive"))
      (node (ref "C387") (pin "1") (pinfunction "1_1") (pintype "passive"))
      (node (ref "C388") (pin "1") (pinfunction "1_1") (pintype "passive"))
      (node (ref "C389") (pin "1") (pinfunction "1_1") (pintype "passive"))
      (node (ref "C390") (pin "1") (pinfunction "1_1") (pintype "passive"))
      (node (ref "C391") (pin "1") (pinfunction "1_1") (pintype "passive"))
      (node (ref "C392") (pin "1") (pinfunction "1_1") (pintype "passive"))
      (node (ref "C393") (pin "1") (pinfunction "1_1") (pintype "passive"))
      (node (ref "C394") (pin "1") (pinfunction "1_1") (pintype "passive"))
      (node (ref "C395") (pin "1") (pinfunction "1_1") (pintype "passive"))
      (node (ref "C396") (pin "1") (pinfunction "1_1") (pintype "passive"))
      (node (ref "C397") (pin "1") (pinfunction "1_1") (pintype "passive"))
      (node (ref "C398") (pin "1") (pinfunction "1_1") (pintype "passive"))
      (node (ref "C399") (pin "1") (pinfunction "1_1") (pintype "passive"))
      (node (ref "C400") (pin "1") (pinfunction "1_1") (pintype "passive"))
      (node (ref "C401") (pin "1") (pinfunction "1_1") (pintype "passive"))
      (node (ref "C402") (pin "1") (pinfunction "1_1") (pintype "passive"))
      (node (ref "C403") (pin "1") (pinfunction "1_1") (pintype "passive"))
      (node (ref "C404") (pin "1") (pinfunction "1_1") (pintype "passive"))
      (node (ref "C405") (pin "1") (pinfunction "1_1") (pintype "passive"))
      (node (ref "C406") (pin "1") (pinfunction "1_1") (pintype "passive"))
      (node (ref "C407") (pin "1") (pinfunction "1_1") (pintype "passive"))
      (node (ref "C408") (pin "1") (pinfunction "1_1") (pintype "passive"))
      (node (ref "C409") (pin "1") (pinfunction "1_1") (pintype "passive"))
      (node (ref "C410") (pin "1") (pinfunction "1_1") (pintype "passive"))
      (node (ref "C411") (pin "1") (pinfunction "1_1") (pintype "passive"))
      (node (ref "C412") (pin "1") (pinfunction "1_1") (pintype "passive"))
      (node (ref "C413") (pin "1") (pinfunction "1_1") (pintype "passive"))
      (node (ref "C414") (pin "1") (pinfunction "1_1") (pintype "passive"))
      (node (ref "C415") (pin "1") (pinfunction "1_1") (pintype "passive"))
      (node (ref "M14") (pin "0") (pinfunction "PIN_0") (pintype "power_in"))
      (node (ref "M15") (pin "0") (pinfunction "PIN_0") (pintype "power_in"))
      (node (ref "M16") (pin "0") (pinfunction "PIN_0") (pintype "power_in"))
      (node (ref "M17") (pin "0") (pinfunction "PIN_0") (pintype "power_in"))
      (node (ref "M18") (pin "0") (pinfunction "PIN_0") (pintype "power_in"))
      (node (ref "U19") (pin "12") (pinfunction "GND_12") (pintype "power_in"))
      (node (ref "U19") (pin "13") (pinfunction "VSS_13") (pintype "power_in"))
      (node (ref "U19") (pin "15") (pinfunction "ADDR0_15") (pintype "passive"))
      (node (ref "U19") (pin "16") (pinfunction "ADDR1_16") (pintype "passive"))
      (node (ref "U19") (pin "18") (pinfunction "GND_18") (pintype "power_in"))
      (node (ref "U19") (pin "19") (pinfunction "ADDR2_19") (pintype "passive"))
      (node (ref "U19") (pin "20") (pinfunction "ADDR3_20") (pintype "passive"))
      (node (ref "U19") (pin "22") (pinfunction "GND_22") (pintype "power_in"))
      (node (ref "U19") (pin "23") (pinfunction "ADDR4_23") (pintype "passive"))
      (node (ref "U19") (pin "24") (pinfunction "ADDR5_24") (pintype "passive"))
      (node (ref "U19") (pin "26") (pinfunction "GND_26") (pintype "power_in"))
      (node (ref "U19") (pin "27") (pinfunction "ADDR6_27") (pintype "passive"))
      (node (ref "U19") (pin "3") (pinfunction "GND_3") (pintype "power_in"))
      (node (ref "U19") (pin "30") (pinfunction "VSS_30") (pintype "power_in"))
      (node (ref "U19") (pin "31") (pinfunction "GND_31") (pintype "power_in"))
      (node (ref "U19") (pin "35") (pinfunction "GND_35") (pintype "power_in"))
      (node (ref "U19") (pin "41") (pinfunction "GND_41") (pintype "power_in"))
      (node (ref "U19") (pin "42") (pinfunction "VSS_42") (pintype "power_in"))
      (node (ref "U19") (pin "45") (pinfunction "SMODE_45") (pintype "passive"))
      (node (ref "U19") (pin "46") (pinfunction "GND_46") (pintype "power_in"))
      (node (ref "U19") (pin "50") (pinfunction "TEST_50") (pintype "passive"))
      (node (ref "U19") (pin "52") (pinfunction "GND_52") (pintype "power_in"))
      (node (ref "U19") (pin "53") (pinfunction "PLL_DVSS_53") (pintype "power_in"))
      (node (ref "U19") (pin "56") (pinfunction "PLL_AVSS_56") (pintype "power_in"))
      (node (ref "U19") (pin "57") (pinfunction "GND_57") (pintype "power_in"))
      (node (ref "U19") (pin "8") (pinfunction "GND_8") (pintype "power_in"))
      (node (ref "U20") (pin "12") (pinfunction "GND_12") (pintype "power_in"))
      (node (ref "U20") (pin "13") (pinfunction "VSS_13") (pintype "power_in"))
      (node (ref "U20") (pin "15") (pinfunction "ADDR0_15") (pintype "passive"))
      (node (ref "U20") (pin "16") (pinfunction "ADDR1_16") (pintype "passive"))
      (node (ref "U20") (pin "18") (pinfunction "GND_18") (pintype "power_in"))
      (node (ref "U20") (pin "19") (pinfunction "ADDR2_19") (pintype "passive"))
      (node (ref "U20") (pin "22") (pinfunction "GND_22") (pintype "power_in"))
      (node (ref "U20") (pin "23") (pinfunction "ADDR4_23") (pintype "passive"))
      (node (ref "U20") (pin "24") (pinfunction "ADDR5_24") (pintype "passive"))
      (node (ref "U20") (pin "26") (pinfunction "GND_26") (pintype "power_in"))
      (node (ref "U20") (pin "27") (pinfunction "ADDR6_27") (pintype "passive"))
      (node (ref "U20") (pin "3") (pinfunction "GND_3") (pintype "power_in"))
      (node (ref "U20") (pin "30") (pinfunction "VSS_30") (pintype "power_in"))
      (node (ref "U20") (pin "31") (pinfunction "GND_31") (pintype "power_in"))
      (node (ref "U20") (pin "35") (pinfunction "GND_35") (pintype "power_in"))
      (node (ref "U20") (pin "41") (pinfunction "GND_41") (pintype "power_in"))
      (node (ref "U20") (pin "42") (pinfunction "VSS_42") (pintype "power_in"))
      (node (ref "U20") (pin "45") (pinfunction "SMODE_45") (pintype "passive"))
      (node (ref "U20") (pin "46") (pinfunction "GND_46") (pintype "power_in"))
      (node (ref "U20") (pin "50") (pinfunction "TEST_50") (pintype "passive"))
      (node (ref "U20") (pin "52") (pinfunction "GND_52") (pintype "power_in"))
      (node (ref "U20") (pin "53") (pinfunction "PLL_DVSS_53") (pintype "power_in"))
      (node (ref "U20") (pin "56") (pinfunction "PLL_AVSS_56") (pintype "power_in"))
      (node (ref "U20") (pin "57") (pinfunction "GND_57") (pintype "power_in"))
      (node (ref "U20") (pin "8") (pinfunction "GND_8") (pintype "power_in"))
      (node (ref "U21") (pin "12") (pinfunction "GND_12") (pintype "power_in"))
      (node (ref "U21") (pin "13") (pinfunction "VSS_13") (pintype "power_in"))
      (node (ref "U21") (pin "15") (pinfunction "ADDR0_15") (pintype "passive"))
      (node (ref "U21") (pin "16") (pinfunction "ADDR1_16") (pintype "passive"))
      (node (ref "U21") (pin "18") (pinfunction "GND_18") (pintype "power_in"))
      (node (ref "U21") (pin "19") (pinfunction "ADDR2_19") (pintype "passive"))
      (node (ref "U21") (pin "20") (pinfunction "ADDR3_20") (pintype "passive"))
      (node (ref "U21") (pin "22") (pinfunction "GND_22") (pintype "power_in"))
      (node (ref "U21") (pin "24") (pinfunction "ADDR5_24") (pintype "passive"))
      (node (ref "U21") (pin "26") (pinfunction "GND_26") (pintype "power_in"))
      (node (ref "U21") (pin "27") (pinfunction "ADDR6_27") (pintype "passive"))
      (node (ref "U21") (pin "3") (pinfunction "GND_3") (pintype "power_in"))
      (node (ref "U21") (pin "30") (pinfunction "VSS_30") (pintype "power_in"))
      (node (ref "U21") (pin "31") (pinfunction "GND_31") (pintype "power_in"))
      (node (ref "U21") (pin "35") (pinfunction "GND_35") (pintype "power_in"))
      (node (ref "U21") (pin "41") (pinfunction "GND_41") (pintype "power_in"))
      (node (ref "U21") (pin "42") (pinfunction "VSS_42") (pintype "power_in"))
      (node (ref "U21") (pin "45") (pinfunction "SMODE_45") (pintype "passive"))
      (node (ref "U21") (pin "46") (pinfunction "GND_46") (pintype "power_in"))
      (node (ref "U21") (pin "50") (pinfunction "TEST_50") (pintype "passive"))
      (node (ref "U21") (pin "52") (pinfunction "GND_52") (pintype "power_in"))
      (node (ref "U21") (pin "53") (pinfunction "PLL_DVSS_53") (pintype "power_in"))
      (node (ref "U21") (pin "56") (pinfunction "PLL_AVSS_56") (pintype "power_in"))
      (node (ref "U21") (pin "57") (pinfunction "GND_57") (pintype "power_in"))
      (node (ref "U21") (pin "8") (pinfunction "GND_8") (pintype "power_in"))
      (node (ref "U22") (pin "12") (pinfunction "GND_12") (pintype "power_in"))
      (node (ref "U22") (pin "13") (pinfunction "VSS_13") (pintype "power_in"))
      (node (ref "U22") (pin "15") (pinfunction "ADDR0_15") (pintype "passive"))
      (node (ref "U22") (pin "16") (pinfunction "ADDR1_16") (pintype "passive"))
      (node (ref "U22") (pin "18") (pinfunction "GND_18") (pintype "power_in"))
      (node (ref "U22") (pin "19") (pinfunction "ADDR2_19") (pintype "passive"))
      (node (ref "U22") (pin "22") (pinfunction "GND_22") (pintype "power_in"))
      (node (ref "U22") (pin "24") (pinfunction "ADDR5_24") (pintype "passive"))
      (node (ref "U22") (pin "26") (pinfunction "GND_26") (pintype "power_in"))
      (node (ref "U22") (pin "27") (pinfunction "ADDR6_27") (pintype "passive"))
      (node (ref "U22") (pin "3") (pinfunction "GND_3") (pintype "power_in"))
      (node (ref "U22") (pin "30") (pinfunction "VSS_30") (pintype "power_in"))
      (node (ref "U22") (pin "31") (pinfunction "GND_31") (pintype "power_in"))
      (node (ref "U22") (pin "35") (pinfunction "GND_35") (pintype "power_in"))
      (node (ref "U22") (pin "41") (pinfunction "GND_41") (pintype "power_in"))
      (node (ref "U22") (pin "42") (pinfunction "VSS_42") (pintype "power_in"))
      (node (ref "U22") (pin "45") (pinfunction "SMODE_45") (pintype "passive"))
      (node (ref "U22") (pin "46") (pinfunction "GND_46") (pintype "power_in"))
      (node (ref "U22") (pin "50") (pinfunction "TEST_50") (pintype "passive"))
      (node (ref "U22") (pin "52") (pinfunction "GND_52") (pintype "power_in"))
      (node (ref "U22") (pin "53") (pinfunction "PLL_DVSS_53") (pintype "power_in"))
      (node (ref "U22") (pin "56") (pinfunction "PLL_AVSS_56") (pintype "power_in"))
      (node (ref "U22") (pin "57") (pinfunction "GND_57") (pintype "power_in"))
      (node (ref "U22") (pin "8") (pinfunction "GND_8") (pintype "power_in"))
      (node (ref "U23") (pin "12") (pinfunction "GND_12") (pintype "power_in"))
      (node (ref "U23") (pin "13") (pinfunction "VSS_13") (pintype "power_in"))
      (node (ref "U23") (pin "15") (pinfunction "ADDR0_15") (pintype "passive"))
      (node (ref "U23") (pin "16") (pinfunction "ADDR1_16") (pintype "passive"))
      (node (ref "U23") (pin "18") (pinfunction "GND_18") (pintype "power_in"))
      (node (ref "U23") (pin "19") (pinfunction "ADDR2_19") (pintype "passive"))
      (node (ref "U23") (pin "20") (pinfunction "ADDR3_20") (pintype "passive"))
      (node (ref "U23") (pin "22") (pinfunction "GND_22") (pintype "power_in"))
      (node (ref "U23") (pin "23") (pinfunction "ADDR4_23") (pintype "passive"))
      (node (ref "U23") (pin "26") (pinfunction "GND_26") (pintype "power_in"))
      (node (ref "U23") (pin "27") (pinfunction "ADDR6_27") (pintype "passive"))
      (node (ref "U23") (pin "3") (pinfunction "GND_3") (pintype "power_in"))
      (node (ref "U23") (pin "30") (pinfunction "VSS_30") (pintype "power_in"))
      (node (ref "U23") (pin "31") (pinfunction "GND_31") (pintype "power_in"))
      (node (ref "U23") (pin "35") (pinfunction "GND_35") (pintype "power_in"))
      (node (ref "U23") (pin "41") (pinfunction "GND_41") (pintype "power_in"))
      (node (ref "U23") (pin "42") (pinfunction "VSS_42") (pintype "power_in"))
      (node (ref "U23") (pin "45") (pinfunction "SMODE_45") (pintype "passive"))
      (node (ref "U23") (pin "46") (pinfunction "GND_46") (pintype "power_in"))
      (node (ref "U23") (pin "50") (pinfunction "TEST_50") (pintype "passive"))
      (node (ref "U23") (pin "52") (pinfunction "GND_52") (pintype "power_in"))
      (node (ref "U23") (pin "53") (pinfunction "PLL_DVSS_53") (pintype "power_in"))
      (node (ref "U23") (pin "56") (pinfunction "PLL_AVSS_56") (pintype "power_in"))
      (node (ref "U23") (pin "57") (pinfunction "GND_57") (pintype "power_in"))
      (node (ref "U23") (pin "8") (pinfunction "GND_8") (pintype "power_in"))
      (node (ref "U24") (pin "12") (pinfunction "GND_12") (pintype "power_in"))
      (node (ref "U24") (pin "13") (pinfunction "VSS_13") (pintype "power_in"))
      (node (ref "U24") (pin "15") (pinfunction "ADDR0_15") (pintype "passive"))
      (node (ref "U24") (pin "16") (pinfunction "ADDR1_16") (pintype "passive"))
      (node (ref "U24") (pin "18") (pinfunction "GND_18") (pintype "power_in"))
      (node (ref "U24") (pin "19") (pinfunction "ADDR2_19") (pintype "passive"))
      (node (ref "U24") (pin "22") (pinfunction "GND_22") (pintype "power_in"))
      (node (ref "U24") (pin "23") (pinfunction "ADDR4_23") (pintype "passive"))
      (node (ref "U24") (pin "26") (pinfunction "GND_26") (pintype "power_in"))
      (node (ref "U24") (pin "27") (pinfunction "ADDR6_27") (pintype "passive"))
      (node (ref "U24") (pin "3") (pinfunction "GND_3") (pintype "power_in"))
      (node (ref "U24") (pin "30") (pinfunction "VSS_30") (pintype "power_in"))
      (node (ref "U24") (pin "31") (pinfunction "GND_31") (pintype "power_in"))
      (node (ref "U24") (pin "35") (pinfunction "GND_35") (pintype "power_in"))
      (node (ref "U24") (pin "41") (pinfunction "GND_41") (pintype "power_in"))
      (node (ref "U24") (pin "42") (pinfunction "VSS_42") (pintype "power_in"))
      (node (ref "U24") (pin "45") (pinfunction "SMODE_45") (pintype "passive"))
      (node (ref "U24") (pin "46") (pinfunction "GND_46") (pintype "power_in"))
      (node (ref "U24") (pin "50") (pinfunction "TEST_50") (pintype "passive"))
      (node (ref "U24") (pin "52") (pinfunction "GND_52") (pintype "power_in"))
      (node (ref "U24") (pin "53") (pinfunction "PLL_DVSS_53") (pintype "power_in"))
      (node (ref "U24") (pin "56") (pinfunction "PLL_AVSS_56") (pintype "power_in"))
      (node (ref "U24") (pin "57") (pinfunction "GND_57") (pintype "power_in"))
      (node (ref "U24") (pin "8") (pinfunction "GND_8") (pintype "power_in"))
      (node (ref "U25") (pin "12") (pinfunction "GND_12") (pintype "power_in"))
      (node (ref "U25") (pin "13") (pinfunction "VSS_13") (pintype "power_in"))
      (node (ref "U25") (pin "15") (pinfunction "ADDR0_15") (pintype "passive"))
      (node (ref "U25") (pin "16") (pinfunction "ADDR1_16") (pintype "passive"))
      (node (ref "U25") (pin "18") (pinfunction "GND_18") (pintype "power_in"))
      (node (ref "U25") (pin "19") (pinfunction "ADDR2_19") (pintype "passive"))
      (node (ref "U25") (pin "20") (pinfunction "ADDR3_20") (pintype "passive"))
      (node (ref "U25") (pin "22") (pinfunction "GND_22") (pintype "power_in"))
      (node (ref "U25") (pin "26") (pinfunction "GND_26") (pintype "power_in"))
      (node (ref "U25") (pin "27") (pinfunction "ADDR6_27") (pintype "passive"))
      (node (ref "U25") (pin "3") (pinfunction "GND_3") (pintype "power_in"))
      (node (ref "U25") (pin "30") (pinfunction "VSS_30") (pintype "power_in"))
      (node (ref "U25") (pin "31") (pinfunction "GND_31") (pintype "power_in"))
      (node (ref "U25") (pin "35") (pinfunction "GND_35") (pintype "power_in"))
      (node (ref "U25") (pin "41") (pinfunction "GND_41") (pintype "power_in"))
      (node (ref "U25") (pin "42") (pinfunction "VSS_42") (pintype "power_in"))
      (node (ref "U25") (pin "45") (pinfunction "SMODE_45") (pintype "passive"))
      (node (ref "U25") (pin "46") (pinfunction "GND_46") (pintype "power_in"))
      (node (ref "U25") (pin "50") (pinfunction "TEST_50") (pintype "passive"))
      (node (ref "U25") (pin "52") (pinfunction "GND_52") (pintype "power_in"))
      (node (ref "U25") (pin "53") (pinfunction "PLL_DVSS_53") (pintype "power_in"))
      (node (ref "U25") (pin "56") (pinfunction "PLL_AVSS_56") (pintype "power_in"))
      (node (ref "U25") (pin "57") (pinfunction "GND_57") (pintype "power_in"))
      (node (ref "U25") (pin "8") (pinfunction "GND_8") (pintype "power_in"))
      (node (ref "U26") (pin "12") (pinfunction "GND_12") (pintype "power_in"))
      (node (ref "U26") (pin "13") (pinfunction "VSS_13") (pintype "power_in"))
      (node (ref "U26") (pin "15") (pinfunction "ADDR0_15") (pintype "passive"))
      (node (ref "U26") (pin "16") (pinfunction "ADDR1_16") (pintype "passive"))
      (node (ref "U26") (pin "18") (pinfunction "GND_18") (pintype "power_in"))
      (node (ref "U26") (pin "19") (pinfunction "ADDR2_19") (pintype "passive"))
      (node (ref "U26") (pin "22") (pinfunction "GND_22") (pintype "power_in"))
      (node (ref "U26") (pin "26") (pinfunction "GND_26") (pintype "power_in"))
      (node (ref "U26") (pin "27") (pinfunction "ADDR6_27") (pintype "passive"))
      (node (ref "U26") (pin "3") (pinfunction "GND_3") (pintype "power_in"))
      (node (ref "U26") (pin "30") (pinfunction "VSS_30") (pintype "power_in"))
      (node (ref "U26") (pin "31") (pinfunction "GND_31") (pintype "power_in"))
      (node (ref "U26") (pin "35") (pinfunction "GND_35") (pintype "power_in"))
      (node (ref "U26") (pin "41") (pinfunction "GND_41") (pintype "power_in"))
      (node (ref "U26") (pin "42") (pinfunction "VSS_42") (pintype "power_in"))
      (node (ref "U26") (pin "45") (pinfunction "SMODE_45") (pintype "passive"))
      (node (ref "U26") (pin "46") (pinfunction "GND_46") (pintype "power_in"))
      (node (ref "U26") (pin "50") (pinfunction "TEST_50") (pintype "passive"))
      (node (ref "U26") (pin "52") (pinfunction "GND_52") (pintype "power_in"))
      (node (ref "U26") (pin "53") (pinfunction "PLL_DVSS_53") (pintype "power_in"))
      (node (ref "U26") (pin "56") (pinfunction "PLL_AVSS_56") (pintype "power_in"))
      (node (ref "U26") (pin "57") (pinfunction "GND_57") (pintype "power_in"))
      (node (ref "U26") (pin "8") (pinfunction "GND_8") (pintype "power_in"))
    )
    (net (code "48") (name "Net-(U19-PLL_AVDD)") (class "Default")
      (node (ref "C289") (pin "2") (pinfunction "2_2") (pintype "passive"))
      (node (ref "FB17") (pin "1") (pinfunction "1_1") (pintype "passive"))
      (node (ref "U19") (pin "55") (pinfunction "PLL_AVDD_55") (pintype "power_in"))
    )
    (net (code "49") (name "Net-(U20-PLL_AVDD)") (class "Default")
      (node (ref "C291") (pin "2") (pinfunction "2_2") (pintype "passive"))
      (node (ref "FB18") (pin "1") (pinfunction "1_1") (pintype "passive"))
      (node (ref "U20") (pin "55") (pinfunction "PLL_AVDD_55") (pintype "power_in"))
    )
    (net (code "50") (name "Net-(U21-PLL_AVDD)") (class "Default")
      (node (ref "C293") (pin "2") (pinfunction "2_2") (pintype "passive"))
      (node (ref "FB19") (pin "1") (pinfunction "1_1") (pintype "passive"))
      (node (ref "U21") (pin "55") (pinfunction "PLL_AVDD_55") (pintype "power_in"))
    )
    (net (code "51") (name "Net-(U22-PLL_AVDD)") (class "Default")
      (node (ref "C295") (pin "2") (pinfunction "2_2") (pintype "passive"))
      (node (ref "FB20") (pin "1") (pinfunction "1_1") (pintype "passive"))
      (node (ref "U22") (pin "55") (pinfunction "PLL_AVDD_55") (pintype "power_in"))
    )
    (net (code "52") (name "Net-(U23-PLL_AVDD)") (class "Default")
      (node (ref "C353") (pin "2") (pinfunction "2_2") (pintype "passive"))
      (node (ref "FB21") (pin "1") (pinfunction "1_1") (pintype "passive"))
      (node (ref "U23") (pin "55") (pinfunction "PLL_AVDD_55") (pintype "power_in"))
    )
    (net (code "53") (name "Net-(U24-PLL_AVDD)") (class "Default")
      (node (ref "C355") (pin "2") (pinfunction "2_2") (pintype "passive"))
      (node (ref "FB22") (pin "1") (pinfunction "1_1") (pintype "passive"))
      (node (ref "U24") (pin "55") (pinfunction "PLL_AVDD_55") (pintype "power_in"))
    )
    (net (code "54") (name "Net-(U25-PLL_AVDD)") (class "Default")
      (node (ref "C357") (pin "2") (pinfunction "2_2") (pintype "passive"))
      (node (ref "FB23") (pin "1") (pinfunction "1_1") (pintype "passive"))
      (node (ref "U25") (pin "55") (pinfunction "PLL_AVDD_55") (pintype "power_in"))
    )
    (net (code "55") (name "Net-(U26-PLL_AVDD)") (class "Default")
      (node (ref "C359") (pin "2") (pinfunction "2_2") (pintype "passive"))
      (node (ref "FB24") (pin "1") (pinfunction "1_1") (pintype "passive"))
      (node (ref "U26") (pin "55") (pinfunction "PLL_AVDD_55") (pintype "power_in"))
    )
    (net (code "56") (name "VDD3") (class "Default")
      (node (ref "C284") (pin "1") (pinfunction "1_1") (pintype "passive"))
      (node (ref "C285") (pin "1") (pinfunction "1_1") (pintype "passive"))
      (node (ref "C286") (pin "2") (pinfunction "2_2") (pintype "passive"))
      (node (ref "C287") (pin "2") (pinfunction "2_2") (pintype "passive"))
      (node (ref "C308") (pin "2") (pinfunction "2_2") (pintype "passive"))
      (node (ref "C309") (pin "2") (pinfunction "2_2") (pintype "passive"))
      (node (ref "C310") (pin "2") (pinfunction "2_2") (pintype "passive"))
      (node (ref "C311") (pin "2") (pinfunction "2_2") (pintype "passive"))
      (node (ref "C312") (pin "2") (pinfunction "2_2") (pintype "passive"))
      (node (ref "C313") (pin "2") (pinfunction "2_2") (pintype "passive"))
      (node (ref "C314") (pin "2") (pinfunction "2_2") (pintype "passive"))
      (node (ref "C315") (pin "2") (pinfunction "2_2") (pintype "passive"))
      (node (ref "C316") (pin "2") (pinfunction "2_2") (pintype "passive"))
      (node (ref "C317") (pin "2") (pinfunction "2_2") (pintype "passive"))
      (node (ref "C318") (pin "2") (pinfunction "2_2") (pintype "passive"))
      (node (ref "C319") (pin "2") (pinfunction "2_2") (pintype "passive"))
      (node (ref "C320") (pin "2") (pinfunction "2_2") (pintype "passive"))
      (node (ref "C321") (pin "2") (pinfunction "2_2") (pintype "passive"))
      (node (ref "C322") (pin "2") (pinfunction "2_2") (pintype "passive"))
      (node (ref "C323") (pin "2") (pinfunction "2_2") (pintype "passive"))
      (node (ref "C324") (pin "2") (pinfunction "2_2") (pintype "passive"))
      (node (ref "C325") (pin "2") (pinfunction "2_2") (pintype "passive"))
      (node (ref "C326") (pin "2") (pinfunction "2_2") (pintype "passive"))
      (node (ref "C327") (pin "2") (pinfunction "2_2") (pintype "passive"))
      (node (ref "C328") (pin "2") (pinfunction "2_2") (pintype "passive"))
      (node (ref "C329") (pin "2") (pinfunction "2_2") (pintype "passive"))
      (node (ref "C330") (pin "2") (pinfunction "2_2") (pintype "passive"))
      (node (ref "C331") (pin "2") (pinfunction "2_2") (pintype "passive"))
      (node (ref "C332") (pin "2") (pinfunction "2_2") (pintype "passive"))
      (node (ref "C333") (pin "2") (pinfunction "2_2") (pintype "passive"))
      (node (ref "C334") (pin "2") (pinfunction "2_2") (pintype "passive"))
      (node (ref "C335") (pin "2") (pinfunction "2_2") (pintype "passive"))
      (node (ref "C336") (pin "2") (pinfunction "2_2") (pintype "passive"))
      (node (ref "C337") (pin "2") (pinfunction "2_2") (pintype "passive"))
      (node (ref "C338") (pin "2") (pinfunction "2_2") (pintype "passive"))
      (node (ref "C339") (pin "2") (pinfunction "2_2") (pintype "passive"))
      (node (ref "C340") (pin "2") (pinfunction "2_2") (pintype "passive"))
      (node (ref "C341") (pin "2") (pinfunction "2_2") (pintype "passive"))
      (node (ref "C342") (pin "2") (pinfunction "2_2") (pintype "passive"))
      (node (ref "C343") (pin "2") (pinfunction "2_2") (pintype "passive"))
      (node (ref "C344") (pin "2") (pinfunction "2_2") (pintype "passive"))
      (node (ref "C345") (pin "2") (pinfunction "2_2") (pintype "passive"))
      (node (ref "C346") (pin "2") (pinfunction "2_2") (pintype "passive"))
      (node (ref "C347") (pin "2") (pinfunction "2_2") (pintype "passive"))
      (node (ref "C348") (pin "2") (pinfunction "2_2") (pintype "passive"))
      (node (ref "C349") (pin "2") (pinfunction "2_2") (pintype "passive"))
      (node (ref "C350") (pin "2") (pinfunction "2_2") (pintype "passive"))
      (node (ref "C351") (pin "2") (pinfunction "2_2") (pintype "passive"))
      (node (ref "C372") (pin "2") (pinfunction "2_2") (pintype "passive"))
      (node (ref "C373") (pin "2") (pinfunction "2_2") (pintype "passive"))
      (node (ref "C374") (pin "2") (pinfunction "2_2") (pintype "passive"))
      (node (ref "C375") (pin "2") (pinfunction "2_2") (pintype "passive"))
      (node (ref "C376") (pin "2") (pinfunction "2_2") (pintype "passive"))
      (node (ref "C377") (pin "2") (pinfunction "2_2") (pintype "passive"))
      (node (ref "C378") (pin "2") (pinfunction "2_2") (pintype "passive"))
      (node (ref "C379") (pin "2") (pinfunction "2_2") (pintype "passive"))
      (node (ref "C380") (pin "2") (pinfunction "2_2") (pintype "passive"))
      (node (ref "C381") (pin "2") (pinfunction "2_2") (pintype "passive"))
      (node (ref "C382") (pin "2") (pinfunction "2_2") (pintype "passive"))
      (node (ref "C383") (pin "2") (pinfunction "2_2") (pintype "passive"))
      (node (ref "C384") (pin "2") (pinfunction "2_2") (pintype "passive"))
      (node (ref "C385") (pin "2") (pinfunction "2_2") (pintype "passive"))
      (node (ref "C386") (pin "2") (pinfunction "2_2") (pintype "passive"))
      (node (ref "C387") (pin "2") (pinfunction "2_2") (pintype "passive"))
      (node (ref "C388") (pin "2") (pinfunction "2_2") (pintype "passive"))
      (node (ref "C389") (pin "2") (pinfunction "2_2") (pintype "passive"))
      (node (ref "C390") (pin "2") (pinfunction "2_2") (pintype "passive"))
      (node (ref "C391") (pin "2") (pinfunction "2_2") (pintype "passive"))
      (node (ref "C392") (pin "2") (pinfunction "2_2") (pintype "passive"))
      (node (ref "C393") (pin "2") (pinfunction "2_2") (pintype "passive"))
      (node (ref "C394") (pin "2") (pinfunction "2_2") (pintype "passive"))
      (node (ref "C395") (pin "2") (pinfunction "2_2") (pintype "passive"))
      (node (ref "C396") (pin "2") (pinfunction "2_2") (pintype "passive"))
      (node (ref "C397") (pin "2") (pinfunction "2_2") (pintype "passive"))
      (node (ref "C398") (pin "2") (pinfunction "2_2") (pintype "passive"))
      (node (ref "C399") (pin "2") (pinfunction "2_2") (pintype "passive"))
      (node (ref "C400") (pin "2") (pinfunction "2_2") (pintype "passive"))
      (node (ref "C401") (pin "2") (pinfunction "2_2") (pintype "passive"))
      (node (ref "C402") (pin "2") (pinfunction "2_2") (pintype "passive"))
      (node (ref "C403") (pin "2") (pinfunction "2_2") (pintype "passive"))
      (node (ref "C404") (pin "2") (pinfunction "2_2") (pintype "passive"))
      (node (ref "C405") (pin "2") (pinfunction "2_2") (pintype "passive"))
      (node (ref "C406") (pin "2") (pinfunction "2_2") (pintype "passive"))
      (node (ref "C407") (pin "2") (pinfunction "2_2") (pintype "passive"))
      (node (ref "C408") (pin "2") (pinfunction "2_2") (pintype "passive"))
      (node (ref "C409") (pin "2") (pinfunction "2_2") (pintype "passive"))
      (node (ref "C410") (pin "2") (pinfunction "2_2") (pintype "passive"))
      (node (ref "C411") (pin "2") (pinfunction "2_2") (pintype "passive"))
      (node (ref "C412") (pin "2") (pinfunction "2_2") (pintype "passive"))
      (node (ref "C413") (pin "2") (pinfunction "2_2") (pintype "passive"))
      (node (ref "C414") (pin "2") (pinfunction "2_2") (pintype "passive"))
      (node (ref "C415") (pin "2") (pinfunction "2_2") (pintype "passive"))
      (node (ref "U19") (pin "11") (pinfunction "VDD_11") (pintype "power_in"))
      (node (ref "U19") (pin "17") (pinfunction "VDD_17") (pintype "power_in"))
      (node (ref "U19") (pin "21") (pinfunction "VDD_21") (pintype "power_in"))
      (node (ref "U19") (pin "25") (pinfunction "VDD_25") (pintype "power_in"))
      (node (ref "U19") (pin "32") (pinfunction "VDD_32") (pintype "power_in"))
      (node (ref "U19") (pin "36") (pinfunction "VDD_36") (pintype "power_in"))
      (node (ref "U19") (pin "4") (pinfunction "VDD_4") (pintype "power_in"))
      (node (ref "U19") (pin "40") (pinfunction "VDD_40") (pintype "power_in"))
      (node (ref "U19") (pin "47") (pinfunction "VDD_47") (pintype "power_in"))
      (node (ref "U19") (pin "51") (pinfunction "VDD_51") (pintype "power_in"))
      (node (ref "U19") (pin "7") (pinfunction "VDD_7") (pintype "power_in"))
      (node (ref "U20") (pin "11") (pinfunction "VDD_11") (pintype "power_in"))
      (node (ref "U20") (pin "17") (pinfunction "VDD_17") (pintype "power_in"))
      (node (ref "U20") (pin "21") (pinfunction "VDD_21") (pintype "power_in"))
      (node (ref "U20") (pin "25") (pinfunction "VDD_25") (pintype "power_in"))
      (node (ref "U20") (pin "32") (pinfunction "VDD_32") (pintype "power_in"))
      (node (ref "U20") (pin "36") (pinfunction "VDD_36") (pintype "power_in"))
      (node (ref "U20") (pin "4") (pinfunction "VDD_4") (pintype "power_in"))
      (node (ref "U20") (pin "40") (pinfunction "VDD_40") (pintype "power_in"))
      (node (ref "U20") (pin "47") (pinfunction "VDD_47") (pintype "power_in"))
      (node (ref "U20") (pin "51") (pinfunction "VDD_51") (pintype "power_in"))
      (node (ref "U20") (pin "7") (pinfunction "VDD_7") (pintype "power_in"))
      (node (ref "U21") (pin "11") (pinfunction "VDD_11") (pintype "power_in"))
      (node (ref "U21") (pin "17") (pinfunction "VDD_17") (pintype "power_in"))
      (node (ref "U21") (pin "21") (pinfunction "VDD_21") (pintype "power_in"))
      (node (ref "U21") (pin "25") (pinfunction "VDD_25") (pintype "power_in"))
      (node (ref "U21") (pin "32") (pinfunction "VDD_32") (pintype "power_in"))
      (node (ref "U21") (pin "36") (pinfunction "VDD_36") (pintype "power_in"))
      (node (ref "U21") (pin "4") (pinfunction "VDD_4") (pintype "power_in"))
      (node (ref "U21") (pin "40") (pinfunction "VDD_40") (pintype "power_in"))
      (node (ref "U21") (pin "47") (pinfunction "VDD_47") (pintype "power_in"))
      (node (ref "U21") (pin "51") (pinfunction "VDD_51") (pintype "power_in"))
      (node (ref "U21") (pin "7") (pinfunction "VDD_7") (pintype "power_in"))
      (node (ref "U22") (pin "11") (pinfunction "VDD_11") (pintype "power_in"))
      (node (ref "U22") (pin "17") (pinfunction "VDD_17") (pintype "power_in"))
      (node (ref "U22") (pin "21") (pinfunction "VDD_21") (pintype "power_in"))
      (node (ref "U22") (pin "25") (pinfunction "VDD_25") (pintype "power_in"))
      (node (ref "U22") (pin "32") (pinfunction "VDD_32") (pintype "power_in"))
      (node (ref "U22") (pin "36") (pinfunction "VDD_36") (pintype "power_in"))
      (node (ref "U22") (pin "4") (pinfunction "VDD_4") (pintype "power_in"))
      (node (ref "U22") (pin "40") (pinfunction "VDD_40") (pintype "power_in"))
      (node (ref "U22") (pin "47") (pinfunction "VDD_47") (pintype "power_in"))
      (node (ref "U22") (pin "51") (pinfunction "VDD_51") (pintype "power_in"))
      (node (ref "U22") (pin "7") (pinfunction "VDD_7") (pintype "power_in"))
      (node (ref "U23") (pin "11") (pinfunction "VDD_11") (pintype "power_in"))
      (node (ref "U23") (pin "17") (pinfunction "VDD_17") (pintype "power_in"))
      (node (ref "U23") (pin "21") (pinfunction "VDD_21") (pintype "power_in"))
      (node (ref "U23") (pin "25") (pinfunction "VDD_25") (pintype "power_in"))
      (node (ref "U23") (pin "32") (pinfunction "VDD_32") (pintype "power_in"))
      (node (ref "U23") (pin "36") (pinfunction "VDD_36") (pintype "power_in"))
      (node (ref "U23") (pin "4") (pinfunction "VDD_4") (pintype "power_in"))
      (node (ref "U23") (pin "40") (pinfunction "VDD_40") (pintype "power_in"))
      (node (ref "U23") (pin "47") (pinfunction "VDD_47") (pintype "power_in"))
      (node (ref "U23") (pin "51") (pinfunction "VDD_51") (pintype "power_in"))
      (node (ref "U23") (pin "7") (pinfunction "VDD_7") (pintype "power_in"))
      (node (ref "U24") (pin "11") (pinfunction "VDD_11") (pintype "power_in"))
      (node (ref "U24") (pin "17") (pinfunction "VDD_17") (pintype "power_in"))
      (node (ref "U24") (pin "21") (pinfunction "VDD_21") (pintype "power_in"))
      (node (ref "U24") (pin "25") (pinfunction "VDD_25") (pintype "power_in"))
      (node (ref "U24") (pin "32") (pinfunction "VDD_32") (pintype "power_in"))
      (node (ref "U24") (pin "36") (pinfunction "VDD_36") (pintype "power_in"))
      (node (ref "U24") (pin "4") (pinfunction "VDD_4") (pintype "power_in"))
      (node (ref "U24") (pin "40") (pinfunction "VDD_40") (pintype "power_in"))
      (node (ref "U24") (pin "47") (pinfunction "VDD_47") (pintype "power_in"))
      (node (ref "U24") (pin "51") (pinfunction "VDD_51") (pintype "power_in"))
      (node (ref "U24") (pin "7") (pinfunction "VDD_7") (pintype "power_in"))
      (node (ref "U25") (pin "11") (pinfunction "VDD_11") (pintype "power_in"))
      (node (ref "U25") (pin "17") (pinfunction "VDD_17") (pintype "power_in"))
      (node (ref "U25") (pin "21") (pinfunction "VDD_21") (pintype "power_in"))
      (node (ref "U25") (pin "25") (pinfunction "VDD_25") (pintype "power_in"))
      (node (ref "U25") (pin "32") (pinfunction "VDD_32") (pintype "power_in"))
      (node (ref "U25") (pin "36") (pinfunction "VDD_36") (pintype "power_in"))
      (node (ref "U25") (pin "4") (pinfunction "VDD_4") (pintype "power_in"))
      (node (ref "U25") (pin "40") (pinfunction "VDD_40") (pintype "power_in"))
      (node (ref "U25") (pin "47") (pinfunction "VDD_47") (pintype "power_in"))
      (node (ref "U25") (pin "51") (pinfunction "VDD_51") (pintype "power_in"))
      (node (ref "U25") (pin "7") (pinfunction "VDD_7") (pintype "power_in"))
      (node (ref "U26") (pin "11") (pinfunction "VDD_11") (pintype "power_in"))
      (node (ref "U26") (pin "17") (pinfunction "VDD_17") (pintype "power_in"))
      (node (ref "U26") (pin "21") (pinfunction "VDD_21") (pintype "power_in"))
      (node (ref "U26") (pin "25") (pinfunction "VDD_25") (pintype "power_in"))
      (node (ref "U26") (pin "32") (pinfunction "VDD_32") (pintype "power_in"))
      (node (ref "U26") (pin "36") (pinfunction "VDD_36") (pintype "power_in"))
      (node (ref "U26") (pin "4") (pinfunction "VDD_4") (pintype "power_in"))
      (node (ref "U26") (pin "40") (pinfunction "VDD_40") (pintype "power_in"))
      (node (ref "U26") (pin "47") (pinfunction "VDD_47") (pintype "power_in"))
      (node (ref "U26") (pin "51") (pinfunction "VDD_51") (pintype "power_in"))
      (node (ref "U26") (pin "7") (pinfunction "VDD_7") (pintype "power_in"))
    )
    (net (code "57") (name "VPLL3") (class "Default")
      (node (ref "C288") (pin "1") (pinfunction "1_1") (pintype "passive"))
      (node (ref "C290") (pin "1") (pinfunction "1_1") (pintype "passive"))
      (node (ref "C292") (pin "1") (pinfunction "1_1") (pintype "passive"))
      (node (ref "C294") (pin "1") (pinfunction "1_1") (pintype "passive"))
      (node (ref "C352") (pin "1") (pinfunction "1_1") (pintype "passive"))
      (node (ref "C354") (pin "1") (pinfunction "1_1") (pintype "passive"))
      (node (ref "C356") (pin "1") (pinfunction "1_1") (pintype "passive"))
      (node (ref "C358") (pin "1") (pinfunction "1_1") (pintype "passive"))
      (node (ref "FB17") (pin "2") (pinfunction "2_2") (pintype "passive"))
      (node (ref "FB18") (pin "2") (pinfunction "2_2") (pintype "passive"))
      (node (ref "FB19") (pin "2") (pinfunction "2_2") (pintype "passive"))
      (node (ref "FB20") (pin "2") (pinfunction "2_2") (pintype "passive"))
      (node (ref "FB21") (pin "2") (pinfunction "2_2") (pintype "passive"))
      (node (ref "FB22") (pin "2") (pinfunction "2_2") (pintype "passive"))
      (node (ref "FB23") (pin "2") (pinfunction "2_2") (pintype "passive"))
      (node (ref "FB24") (pin "2") (pinfunction "2_2") (pintype "passive"))
      (node (ref "U19") (pin "54") (pinfunction "PLL_DVDD_54") (pintype "power_in"))
      (node (ref "U20") (pin "54") (pinfunction "PLL_DVDD_54") (pintype "power_in"))
      (node (ref "U21") (pin "54") (pinfunction "PLL_DVDD_54") (pintype "power_in"))
      (node (ref "U22") (pin "54") (pinfunction "PLL_DVDD_54") (pintype "power_in"))
      (node (ref "U23") (pin "54") (pinfunction "PLL_DVDD_54") (pintype "power_in"))
      (node (ref "U24") (pin "54") (pinfunction "PLL_DVDD_54") (pintype "power_in"))
      (node (ref "U25") (pin "54") (pinfunction "PLL_DVDD_54") (pintype "power_in"))
      (node (ref "U26") (pin "54") (pinfunction "PLL_DVDD_54") (pintype "power_in"))
    )
    (net (code "58") (name "unconnected-(U19-CMODE-Pad44)") (class "Default")
      (node (ref "U19") (pin "44") (pinfunction "CMODE_44") (pintype "passive+no_connect"))
    )
    (net (code "59") (name "unconnected-(U19-RF-Pad49)") (class "Default")
      (node (ref "U19") (pin "49") (pinfunction "RF_49") (pintype "output+no_connect"))
    )
    (net (code "60") (name "unconnected-(U19-TF-Pad48)") (class "Default")
      (node (ref "U19") (pin "48") (pinfunction "TF_48") (pintype "output+no_connect"))
    )
    (net (code "61") (name "unconnected-(U19-XOUT-Pad2)") (class "Default")
      (node (ref "U19") (pin "2") (pinfunction "XOUT_2") (pintype "output+no_connect"))
    )
    (net (code "62") (name "unconnected-(U20-CMODE-Pad44)") (class "Default")
      (node (ref "U20") (pin "44") (pinfunction "CMODE_44") (pintype "passive+no_connect"))
    )
    (net (code "63") (name "unconnected-(U20-RF-Pad49)") (class "Default")
      (node (ref "U20") (pin "49") (pinfunction "RF_49") (pintype "output+no_connect"))
    )
    (net (code "64") (name "unconnected-(U20-TF-Pad48)") (class "Default")
      (node (ref "U20") (pin "48") (pinfunction "TF_48") (pintype "output+no_connect"))
    )
    (net (code "65") (name "unconnected-(U20-XOUT-Pad2)") (class "Default")
      (node (ref "U20") (pin "2") (pinfunction "XOUT_2") (pintype "output+no_connect"))
    )
    (net (code "66") (name "unconnected-(U21-CMODE-Pad44)") (class "Default")
      (node (ref "U21") (pin "44") (pinfunction "CMODE_44") (pintype "passive+no_connect"))
    )
    (net (code "67") (name "unconnected-(U21-RF-Pad49)") (class "Default")
      (node (ref "U21") (pin "49") (pinfunction "RF_49") (pintype "output+no_connect"))
    )
    (net (code "68") (name "unconnected-(U21-TF-Pad48)") (class "Default")
      (node (ref "U21") (pin "48") (pinfunction "TF_48") (pintype "output+no_connect"))
    )
    (net (code "69") (name "unconnected-(U21-XOUT-Pad2)") (class "Default")
      (node (ref "U21") (pin "2") (pinfunction "XOUT_2") (pintype "output+no_connect"))
    )
    (net (code "70") (name "unconnected-(U22-CMODE-Pad44)") (class "Default")
      (node (ref "U22") (pin "44") (pinfunction "CMODE_44") (pintype "passive+no_connect"))
    )
    (net (code "71") (name "unconnected-(U22-RF-Pad49)") (class "Default")
      (node (ref "U22") (pin "49") (pinfunction "RF_49") (pintype "output+no_connect"))
    )
    (net (code "72") (name "unconnected-(U22-TF-Pad48)") (class "Default")
      (node (ref "U22") (pin "48") (pinfunction "TF_48") (pintype "output+no_connect"))
    )
    (net (code "73") (name "unconnected-(U22-XOUT-Pad2)") (class "Default")
      (node (ref "U22") (pin "2") (pinfunction "XOUT_2") (pintype "output+no_connect"))
    )
    (net (code "74") (name "unconnected-(U23-CMODE-Pad44)") (class "Default")
      (node (ref "U23") (pin "44") (pinfunction "CMODE_44") (pintype "passive+no_connect"))
    )
    (net (code "75") (name "unconnected-(U23-RF-Pad49)") (class "Default")
      (node (ref "U23") (pin "49") (pinfunction "RF_49") (pintype "output+no_connect"))
    )
    (net (code "76") (name "unconnected-(U23-TF-Pad48)") (class "Default")
      (node (ref "U23") (pin "48") (pinfunction "TF_48") (pintype "output+no_connect"))
    )
    (net (code "77") (name "unconnected-(U23-XOUT-Pad2)") (class "Default")
      (node (ref "U23") (pin "2") (pinfunction "XOUT_2") (pintype "output+no_connect"))
    )
    (net (code "78") (name "unconnected-(U24-CMODE-Pad44)") (class "Default")
      (node (ref "U24") (pin "44") (pinfunction "CMODE_44") (pintype "passive+no_connect"))
    )
    (net (code "79") (name "unconnected-(U24-RF-Pad49)") (class "Default")
      (node (ref "U24") (pin "49") (pinfunction "RF_49") (pintype "output+no_connect"))
    )
    (net (code "80") (name "unconnected-(U24-TF-Pad48)") (class "Default")
      (node (ref "U24") (pin "48") (pinfunction "TF_48") (pintype "output+no_connect"))
    )
    (net (code "81") (name "unconnected-(U24-XOUT-Pad2)") (class "Default")
      (node (ref "U24") (pin "2") (pinfunction "XOUT_2") (pintype "output+no_connect"))
    )
    (net (code "82") (name "unconnected-(U25-CMODE-Pad44)") (class "Default")
      (node (ref "U25") (pin "44") (pinfunction "CMODE_44") (pintype "passive+no_connect"))
    )
    (net (code "83") (name "unconnected-(U25-RF-Pad49)") (class "Default")
      (node (ref "U25") (pin "49") (pinfunction "RF_49") (pintype "output+no_connect"))
    )
    (net (code "84") (name "unconnected-(U25-TF-Pad48)") (class "Default")
      (node (ref "U25") (pin "48") (pinfunction "TF_48") (pintype "output+no_connect"))
    )
    (net (code "85") (name "unconnected-(U25-XOUT-Pad2)") (class "Default")
      (node (ref "U25") (pin "2") (pinfunction "XOUT_2") (pintype "output+no_connect"))
    )
    (net (code "86") (name "unconnected-(U26-CMODE-Pad44)") (class "Default")
      (node (ref "U26") (pin "44") (pinfunction "CMODE_44") (pintype "passive+no_connect"))
    )
    (net (code "87") (name "unconnected-(U26-RF-Pad49)") (class "Default")
      (node (ref "U26") (pin "49") (pinfunction "RF_49") (pintype "output+no_connect"))
    )
    (net (code "88") (name "unconnected-(U26-TF-Pad48)") (class "Default")
      (node (ref "U26") (pin "48") (pinfunction "TF_48") (pintype "output+no_connect"))
    )
    (net (code "89") (name "unconnected-(U26-XOUT-Pad2)") (class "Default")
      (node (ref "U26") (pin "2") (pinfunction "XOUT_2") (pintype "output+no_connect"))
    )
  )
)
